# GS_01_Pow.net
KiCad netlist of a schematic drawn in Altium Designer
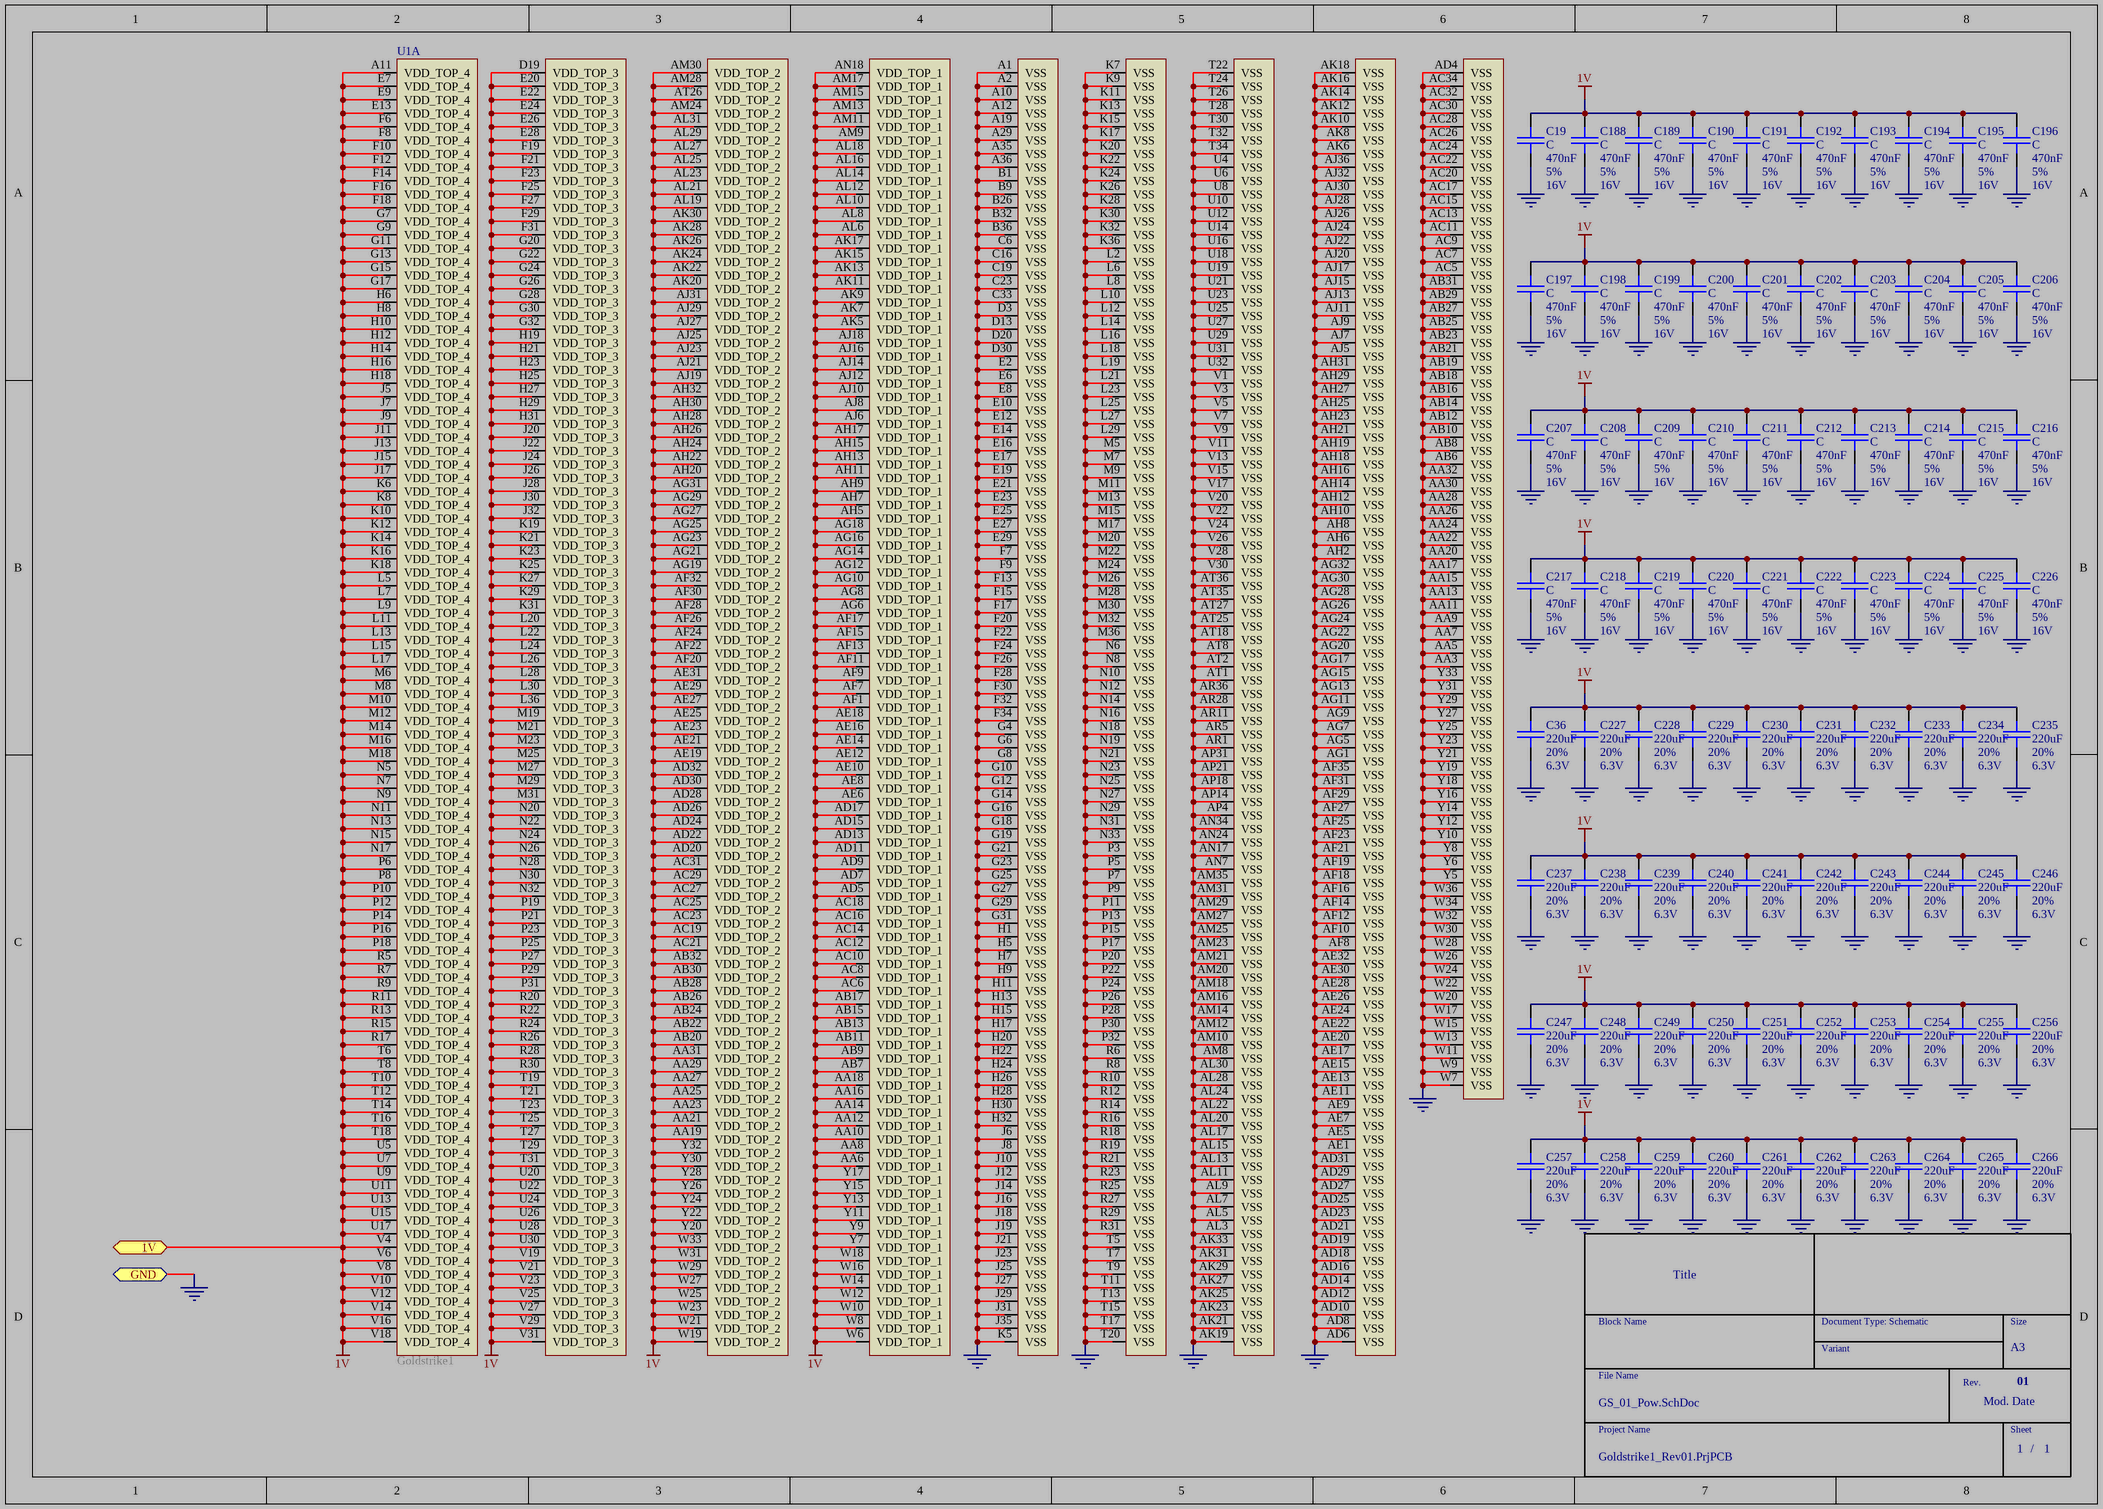
[diagram p0: GS_01_Pow.SchDoc]

(export (version "E")
  (design (tool "Eeschema 10.0.6"))
  (components
    (comp (ref "C19")
      (value "C")
      (footprint "SMD_0603_CAPC1608X95N")
      (fields
        (field (name "DB_PART_NUMBER") "CAP000028169")
        (field (name "DB_VALUE") "470nF")
        (field (name "DB_TOLERANCE") "5%")
        (field (name "DB_VOLTAGE") "16V")
        (field (name "DB_MANUFACTURER_PART") "KEMET    C0603C474J4RAC")
      )
      (libsource (lib "Database_Libs1") (part "C"))
    )
    (comp (ref "C36")
      (value "C")
      (footprint "SMD_1210_CAPC3225X279N")
      (fields
        (field (name "DB_PART_NUMBER") "CAP000047355")
        (field (name "DB_VALUE") "220uF")
        (field (name "DB_TOLERANCE") "20%")
        (field (name "DB_VOLTAGE") "6.3V")
        (field (name "DB_MANUFACTURER_PART") "SAMSUNG    CL32A227MQVNNNE")
        (field (name "DB_APPROVED_BY") "VSN")
      )
      (libsource (lib "Database_Libs1") (part "C"))
    )
    (comp (ref "C188")
      (value "C")
      (footprint "SMD_0603_CAPC1608X95N")
      (fields
        (field (name "DB_PART_NUMBER") "CAP000028169")
        (field (name "DB_VALUE") "470nF")
        (field (name "DB_TOLERANCE") "5%")
        (field (name "DB_VOLTAGE") "16V")
        (field (name "DB_MANUFACTURER_PART") "KEMET    C0603C474J4RAC")
      )
      (libsource (lib "Database_Libs1") (part "C"))
    )
    (comp (ref "C189")
      (value "C")
      (footprint "SMD_0603_CAPC1608X95N")
      (fields
        (field (name "DB_PART_NUMBER") "CAP000028169")
        (field (name "DB_VALUE") "470nF")
        (field (name "DB_TOLERANCE") "5%")
        (field (name "DB_VOLTAGE") "16V")
        (field (name "DB_MANUFACTURER_PART") "KEMET    C0603C474J4RAC")
      )
      (libsource (lib "Database_Libs1") (part "C"))
    )
    (comp (ref "C190")
      (value "C")
      (footprint "SMD_0603_CAPC1608X95N")
      (fields
        (field (name "DB_PART_NUMBER") "CAP000028169")
        (field (name "DB_VALUE") "470nF")
        (field (name "DB_TOLERANCE") "5%")
        (field (name "DB_VOLTAGE") "16V")
        (field (name "DB_MANUFACTURER_PART") "KEMET    C0603C474J4RAC")
      )
      (libsource (lib "Database_Libs1") (part "C"))
    )
    (comp (ref "C191")
      (value "C")
      (footprint "SMD_0603_CAPC1608X95N")
      (fields
        (field (name "DB_PART_NUMBER") "CAP000028169")
        (field (name "DB_VALUE") "470nF")
        (field (name "DB_TOLERANCE") "5%")
        (field (name "DB_VOLTAGE") "16V")
        (field (name "DB_MANUFACTURER_PART") "KEMET    C0603C474J4RAC")
      )
      (libsource (lib "Database_Libs1") (part "C"))
    )
    (comp (ref "C192")
      (value "C")
      (footprint "SMD_0603_CAPC1608X95N")
      (fields
        (field (name "DB_PART_NUMBER") "CAP000028169")
        (field (name "DB_VALUE") "470nF")
        (field (name "DB_TOLERANCE") "5%")
        (field (name "DB_VOLTAGE") "16V")
        (field (name "DB_MANUFACTURER_PART") "KEMET    C0603C474J4RAC")
      )
      (libsource (lib "Database_Libs1") (part "C"))
    )
    (comp (ref "C193")
      (value "C")
      (footprint "SMD_0603_CAPC1608X95N")
      (fields
        (field (name "DB_PART_NUMBER") "CAP000028169")
        (field (name "DB_VALUE") "470nF")
        (field (name "DB_TOLERANCE") "5%")
        (field (name "DB_VOLTAGE") "16V")
        (field (name "DB_MANUFACTURER_PART") "KEMET    C0603C474J4RAC")
      )
      (libsource (lib "Database_Libs1") (part "C"))
    )
    (comp (ref "C194")
      (value "C")
      (footprint "SMD_0603_CAPC1608X95N")
      (fields
        (field (name "DB_PART_NUMBER") "CAP000028169")
        (field (name "DB_VALUE") "470nF")
        (field (name "DB_TOLERANCE") "5%")
        (field (name "DB_VOLTAGE") "16V")
        (field (name "DB_MANUFACTURER_PART") "KEMET    C0603C474J4RAC")
      )
      (libsource (lib "Database_Libs1") (part "C"))
    )
    (comp (ref "C195")
      (value "C")
      (footprint "SMD_0603_CAPC1608X95N")
      (fields
        (field (name "DB_PART_NUMBER") "CAP000028169")
        (field (name "DB_VALUE") "470nF")
        (field (name "DB_TOLERANCE") "5%")
        (field (name "DB_VOLTAGE") "16V")
        (field (name "DB_MANUFACTURER_PART") "KEMET    C0603C474J4RAC")
      )
      (libsource (lib "Database_Libs1") (part "C"))
    )
    (comp (ref "C196")
      (value "C")
      (footprint "SMD_0603_CAPC1608X95N")
      (fields
        (field (name "DB_PART_NUMBER") "CAP000028169")
        (field (name "DB_VALUE") "470nF")
        (field (name "DB_TOLERANCE") "5%")
        (field (name "DB_VOLTAGE") "16V")
        (field (name "DB_MANUFACTURER_PART") "KEMET    C0603C474J4RAC")
      )
      (libsource (lib "Database_Libs1") (part "C"))
    )
    (comp (ref "C197")
      (value "C")
      (footprint "SMD_0603_CAPC1608X95N")
      (fields
        (field (name "DB_PART_NUMBER") "CAP000028169")
        (field (name "DB_VALUE") "470nF")
        (field (name "DB_TOLERANCE") "5%")
        (field (name "DB_VOLTAGE") "16V")
        (field (name "DB_MANUFACTURER_PART") "KEMET    C0603C474J4RAC")
      )
      (libsource (lib "Database_Libs1") (part "C"))
    )
    (comp (ref "C198")
      (value "C")
      (footprint "SMD_0603_CAPC1608X95N")
      (fields
        (field (name "DB_PART_NUMBER") "CAP000028169")
        (field (name "DB_VALUE") "470nF")
        (field (name "DB_TOLERANCE") "5%")
        (field (name "DB_VOLTAGE") "16V")
        (field (name "DB_MANUFACTURER_PART") "KEMET    C0603C474J4RAC")
      )
      (libsource (lib "Database_Libs1") (part "C"))
    )
    (comp (ref "C199")
      (value "C")
      (footprint "SMD_0603_CAPC1608X95N")
      (fields
        (field (name "DB_PART_NUMBER") "CAP000028169")
        (field (name "DB_VALUE") "470nF")
        (field (name "DB_TOLERANCE") "5%")
        (field (name "DB_VOLTAGE") "16V")
        (field (name "DB_MANUFACTURER_PART") "KEMET    C0603C474J4RAC")
      )
      (libsource (lib "Database_Libs1") (part "C"))
    )
    (comp (ref "C200")
      (value "C")
      (footprint "SMD_0603_CAPC1608X95N")
      (fields
        (field (name "DB_PART_NUMBER") "CAP000028169")
        (field (name "DB_VALUE") "470nF")
        (field (name "DB_TOLERANCE") "5%")
        (field (name "DB_VOLTAGE") "16V")
        (field (name "DB_MANUFACTURER_PART") "KEMET    C0603C474J4RAC")
      )
      (libsource (lib "Database_Libs1") (part "C"))
    )
    (comp (ref "C201")
      (value "C")
      (footprint "SMD_0603_CAPC1608X95N")
      (fields
        (field (name "DB_PART_NUMBER") "CAP000028169")
        (field (name "DB_VALUE") "470nF")
        (field (name "DB_TOLERANCE") "5%")
        (field (name "DB_VOLTAGE") "16V")
        (field (name "DB_MANUFACTURER_PART") "KEMET    C0603C474J4RAC")
      )
      (libsource (lib "Database_Libs1") (part "C"))
    )
    (comp (ref "C202")
      (value "C")
      (footprint "SMD_0603_CAPC1608X95N")
      (fields
        (field (name "DB_PART_NUMBER") "CAP000028169")
        (field (name "DB_VALUE") "470nF")
        (field (name "DB_TOLERANCE") "5%")
        (field (name "DB_VOLTAGE") "16V")
        (field (name "DB_MANUFACTURER_PART") "KEMET    C0603C474J4RAC")
      )
      (libsource (lib "Database_Libs1") (part "C"))
    )
    (comp (ref "C203")
      (value "C")
      (footprint "SMD_0603_CAPC1608X95N")
      (fields
        (field (name "DB_PART_NUMBER") "CAP000028169")
        (field (name "DB_VALUE") "470nF")
        (field (name "DB_TOLERANCE") "5%")
        (field (name "DB_VOLTAGE") "16V")
        (field (name "DB_MANUFACTURER_PART") "KEMET    C0603C474J4RAC")
      )
      (libsource (lib "Database_Libs1") (part "C"))
    )
    (comp (ref "C204")
      (value "C")
      (footprint "SMD_0603_CAPC1608X95N")
      (fields
        (field (name "DB_PART_NUMBER") "CAP000028169")
        (field (name "DB_VALUE") "470nF")
        (field (name "DB_TOLERANCE") "5%")
        (field (name "DB_VOLTAGE") "16V")
        (field (name "DB_MANUFACTURER_PART") "KEMET    C0603C474J4RAC")
      )
      (libsource (lib "Database_Libs1") (part "C"))
    )
    (comp (ref "C205")
      (value "C")
      (footprint "SMD_0603_CAPC1608X95N")
      (fields
        (field (name "DB_PART_NUMBER") "CAP000028169")
        (field (name "DB_VALUE") "470nF")
        (field (name "DB_TOLERANCE") "5%")
        (field (name "DB_VOLTAGE") "16V")
        (field (name "DB_MANUFACTURER_PART") "KEMET    C0603C474J4RAC")
      )
      (libsource (lib "Database_Libs1") (part "C"))
    )
    (comp (ref "C206")
      (value "C")
      (footprint "SMD_0603_CAPC1608X95N")
      (fields
        (field (name "DB_PART_NUMBER") "CAP000028169")
        (field (name "DB_VALUE") "470nF")
        (field (name "DB_TOLERANCE") "5%")
        (field (name "DB_VOLTAGE") "16V")
        (field (name "DB_MANUFACTURER_PART") "KEMET    C0603C474J4RAC")
      )
      (libsource (lib "Database_Libs1") (part "C"))
    )
    (comp (ref "C207")
      (value "C")
      (footprint "SMD_0603_CAPC1608X95N")
      (fields
        (field (name "DB_PART_NUMBER") "CAP000028169")
        (field (name "DB_VALUE") "470nF")
        (field (name "DB_TOLERANCE") "5%")
        (field (name "DB_VOLTAGE") "16V")
        (field (name "DB_MANUFACTURER_PART") "KEMET    C0603C474J4RAC")
      )
      (libsource (lib "Database_Libs1") (part "C"))
    )
    (comp (ref "C208")
      (value "C")
      (footprint "SMD_0603_CAPC1608X95N")
      (fields
        (field (name "DB_PART_NUMBER") "CAP000028169")
        (field (name "DB_VALUE") "470nF")
        (field (name "DB_TOLERANCE") "5%")
        (field (name "DB_VOLTAGE") "16V")
        (field (name "DB_MANUFACTURER_PART") "KEMET    C0603C474J4RAC")
      )
      (libsource (lib "Database_Libs1") (part "C"))
    )
    (comp (ref "C209")
      (value "C")
      (footprint "SMD_0603_CAPC1608X95N")
      (fields
        (field (name "DB_PART_NUMBER") "CAP000028169")
        (field (name "DB_VALUE") "470nF")
        (field (name "DB_TOLERANCE") "5%")
        (field (name "DB_VOLTAGE") "16V")
        (field (name "DB_MANUFACTURER_PART") "KEMET    C0603C474J4RAC")
      )
      (libsource (lib "Database_Libs1") (part "C"))
    )
    (comp (ref "C210")
      (value "C")
      (footprint "SMD_0603_CAPC1608X95N")
      (fields
        (field (name "DB_PART_NUMBER") "CAP000028169")
        (field (name "DB_VALUE") "470nF")
        (field (name "DB_TOLERANCE") "5%")
        (field (name "DB_VOLTAGE") "16V")
        (field (name "DB_MANUFACTURER_PART") "KEMET    C0603C474J4RAC")
      )
      (libsource (lib "Database_Libs1") (part "C"))
    )
    (comp (ref "C211")
      (value "C")
      (footprint "SMD_0603_CAPC1608X95N")
      (fields
        (field (name "DB_PART_NUMBER") "CAP000028169")
        (field (name "DB_VALUE") "470nF")
        (field (name "DB_TOLERANCE") "5%")
        (field (name "DB_VOLTAGE") "16V")
        (field (name "DB_MANUFACTURER_PART") "KEMET    C0603C474J4RAC")
      )
      (libsource (lib "Database_Libs1") (part "C"))
    )
    (comp (ref "C212")
      (value "C")
      (footprint "SMD_0603_CAPC1608X95N")
      (fields
        (field (name "DB_PART_NUMBER") "CAP000028169")
        (field (name "DB_VALUE") "470nF")
        (field (name "DB_TOLERANCE") "5%")
        (field (name "DB_VOLTAGE") "16V")
        (field (name "DB_MANUFACTURER_PART") "KEMET    C0603C474J4RAC")
      )
      (libsource (lib "Database_Libs1") (part "C"))
    )
    (comp (ref "C213")
      (value "C")
      (footprint "SMD_0603_CAPC1608X95N")
      (fields
        (field (name "DB_PART_NUMBER") "CAP000028169")
        (field (name "DB_VALUE") "470nF")
        (field (name "DB_TOLERANCE") "5%")
        (field (name "DB_VOLTAGE") "16V")
        (field (name "DB_MANUFACTURER_PART") "KEMET    C0603C474J4RAC")
      )
      (libsource (lib "Database_Libs1") (part "C"))
    )
    (comp (ref "C214")
      (value "C")
      (footprint "SMD_0603_CAPC1608X95N")
      (fields
        (field (name "DB_PART_NUMBER") "CAP000028169")
        (field (name "DB_VALUE") "470nF")
        (field (name "DB_TOLERANCE") "5%")
        (field (name "DB_VOLTAGE") "16V")
        (field (name "DB_MANUFACTURER_PART") "KEMET    C0603C474J4RAC")
      )
      (libsource (lib "Database_Libs1") (part "C"))
    )
    (comp (ref "C215")
      (value "C")
      (footprint "SMD_0603_CAPC1608X95N")
      (fields
        (field (name "DB_PART_NUMBER") "CAP000028169")
        (field (name "DB_VALUE") "470nF")
        (field (name "DB_TOLERANCE") "5%")
        (field (name "DB_VOLTAGE") "16V")
        (field (name "DB_MANUFACTURER_PART") "KEMET    C0603C474J4RAC")
      )
      (libsource (lib "Database_Libs1") (part "C"))
    )
    (comp (ref "C216")
      (value "C")
      (footprint "SMD_0603_CAPC1608X95N")
      (fields
        (field (name "DB_PART_NUMBER") "CAP000028169")
        (field (name "DB_VALUE") "470nF")
        (field (name "DB_TOLERANCE") "5%")
        (field (name "DB_VOLTAGE") "16V")
        (field (name "DB_MANUFACTURER_PART") "KEMET    C0603C474J4RAC")
      )
      (libsource (lib "Database_Libs1") (part "C"))
    )
    (comp (ref "C217")
      (value "C")
      (footprint "SMD_0603_CAPC1608X95N")
      (fields
        (field (name "DB_PART_NUMBER") "CAP000028169")
        (field (name "DB_VALUE") "470nF")
        (field (name "DB_TOLERANCE") "5%")
        (field (name "DB_VOLTAGE") "16V")
        (field (name "DB_MANUFACTURER_PART") "KEMET    C0603C474J4RAC")
      )
      (libsource (lib "Database_Libs1") (part "C"))
    )
    (comp (ref "C218")
      (value "C")
      (footprint "SMD_0603_CAPC1608X95N")
      (fields
        (field (name "DB_PART_NUMBER") "CAP000028169")
        (field (name "DB_VALUE") "470nF")
        (field (name "DB_TOLERANCE") "5%")
        (field (name "DB_VOLTAGE") "16V")
        (field (name "DB_MANUFACTURER_PART") "KEMET    C0603C474J4RAC")
      )
      (libsource (lib "Database_Libs1") (part "C"))
    )
    (comp (ref "C219")
      (value "C")
      (footprint "SMD_0603_CAPC1608X95N")
      (fields
        (field (name "DB_PART_NUMBER") "CAP000028169")
        (field (name "DB_VALUE") "470nF")
        (field (name "DB_TOLERANCE") "5%")
        (field (name "DB_VOLTAGE") "16V")
        (field (name "DB_MANUFACTURER_PART") "KEMET    C0603C474J4RAC")
      )
      (libsource (lib "Database_Libs1") (part "C"))
    )
    (comp (ref "C220")
      (value "C")
      (footprint "SMD_0603_CAPC1608X95N")
      (fields
        (field (name "DB_PART_NUMBER") "CAP000028169")
        (field (name "DB_VALUE") "470nF")
        (field (name "DB_TOLERANCE") "5%")
        (field (name "DB_VOLTAGE") "16V")
        (field (name "DB_MANUFACTURER_PART") "KEMET    C0603C474J4RAC")
      )
      (libsource (lib "Database_Libs1") (part "C"))
    )
    (comp (ref "C221")
      (value "C")
      (footprint "SMD_0603_CAPC1608X95N")
      (fields
        (field (name "DB_PART_NUMBER") "CAP000028169")
        (field (name "DB_VALUE") "470nF")
        (field (name "DB_TOLERANCE") "5%")
        (field (name "DB_VOLTAGE") "16V")
        (field (name "DB_MANUFACTURER_PART") "KEMET    C0603C474J4RAC")
      )
      (libsource (lib "Database_Libs1") (part "C"))
    )
    (comp (ref "C222")
      (value "C")
      (footprint "SMD_0603_CAPC1608X95N")
      (fields
        (field (name "DB_PART_NUMBER") "CAP000028169")
        (field (name "DB_VALUE") "470nF")
        (field (name "DB_TOLERANCE") "5%")
        (field (name "DB_VOLTAGE") "16V")
        (field (name "DB_MANUFACTURER_PART") "KEMET    C0603C474J4RAC")
      )
      (libsource (lib "Database_Libs1") (part "C"))
    )
    (comp (ref "C223")
      (value "C")
      (footprint "SMD_0603_CAPC1608X95N")
      (fields
        (field (name "DB_PART_NUMBER") "CAP000028169")
        (field (name "DB_VALUE") "470nF")
        (field (name "DB_TOLERANCE") "5%")
        (field (name "DB_VOLTAGE") "16V")
        (field (name "DB_MANUFACTURER_PART") "KEMET    C0603C474J4RAC")
      )
      (libsource (lib "Database_Libs1") (part "C"))
    )
    (comp (ref "C224")
      (value "C")
      (footprint "SMD_0603_CAPC1608X95N")
      (fields
        (field (name "DB_PART_NUMBER") "CAP000028169")
        (field (name "DB_VALUE") "470nF")
        (field (name "DB_TOLERANCE") "5%")
        (field (name "DB_VOLTAGE") "16V")
        (field (name "DB_MANUFACTURER_PART") "KEMET    C0603C474J4RAC")
      )
      (libsource (lib "Database_Libs1") (part "C"))
    )
    (comp (ref "C225")
      (value "C")
      (footprint "SMD_0603_CAPC1608X95N")
      (fields
        (field (name "DB_PART_NUMBER") "CAP000028169")
        (field (name "DB_VALUE") "470nF")
        (field (name "DB_TOLERANCE") "5%")
        (field (name "DB_VOLTAGE") "16V")
        (field (name "DB_MANUFACTURER_PART") "KEMET    C0603C474J4RAC")
      )
      (libsource (lib "Database_Libs1") (part "C"))
    )
    (comp (ref "C226")
      (value "C")
      (footprint "SMD_0603_CAPC1608X95N")
      (fields
        (field (name "DB_PART_NUMBER") "CAP000028169")
        (field (name "DB_VALUE") "470nF")
        (field (name "DB_TOLERANCE") "5%")
        (field (name "DB_VOLTAGE") "16V")
        (field (name "DB_MANUFACTURER_PART") "KEMET    C0603C474J4RAC")
      )
      (libsource (lib "Database_Libs1") (part "C"))
    )
    (comp (ref "C227")
      (value "C")
      (footprint "SMD_1210_CAPC3225X279N")
      (fields
        (field (name "DB_PART_NUMBER") "CAP000047355")
        (field (name "DB_VALUE") "220uF")
        (field (name "DB_TOLERANCE") "20%")
        (field (name "DB_VOLTAGE") "6.3V")
        (field (name "DB_MANUFACTURER_PART") "SAMSUNG    CL32A227MQVNNNE")
        (field (name "DB_APPROVED_BY") "VSN")
      )
      (libsource (lib "Database_Libs1") (part "C"))
    )
    (comp (ref "C228")
      (value "C")
      (footprint "SMD_1210_CAPC3225X279N")
      (fields
        (field (name "DB_PART_NUMBER") "CAP000047355")
        (field (name "DB_VALUE") "220uF")
        (field (name "DB_TOLERANCE") "20%")
        (field (name "DB_VOLTAGE") "6.3V")
        (field (name "DB_MANUFACTURER_PART") "SAMSUNG    CL32A227MQVNNNE")
        (field (name "DB_APPROVED_BY") "VSN")
      )
      (libsource (lib "Database_Libs1") (part "C"))
    )
    (comp (ref "C229")
      (value "C")
      (footprint "SMD_1210_CAPC3225X279N")
      (fields
        (field (name "DB_PART_NUMBER") "CAP000047355")
        (field (name "DB_VALUE") "220uF")
        (field (name "DB_TOLERANCE") "20%")
        (field (name "DB_VOLTAGE") "6.3V")
        (field (name "DB_MANUFACTURER_PART") "SAMSUNG    CL32A227MQVNNNE")
        (field (name "DB_APPROVED_BY") "VSN")
      )
      (libsource (lib "Database_Libs1") (part "C"))
    )
    (comp (ref "C230")
      (value "C")
      (footprint "SMD_1210_CAPC3225X279N")
      (fields
        (field (name "DB_PART_NUMBER") "CAP000047355")
        (field (name "DB_VALUE") "220uF")
        (field (name "DB_TOLERANCE") "20%")
        (field (name "DB_VOLTAGE") "6.3V")
        (field (name "DB_MANUFACTURER_PART") "SAMSUNG    CL32A227MQVNNNE")
        (field (name "DB_APPROVED_BY") "VSN")
      )
      (libsource (lib "Database_Libs1") (part "C"))
    )
    (comp (ref "C231")
      (value "C")
      (footprint "SMD_1210_CAPC3225X279N")
      (fields
        (field (name "DB_PART_NUMBER") "CAP000047355")
        (field (name "DB_VALUE") "220uF")
        (field (name "DB_TOLERANCE") "20%")
        (field (name "DB_VOLTAGE") "6.3V")
        (field (name "DB_MANUFACTURER_PART") "SAMSUNG    CL32A227MQVNNNE")
        (field (name "DB_APPROVED_BY") "VSN")
      )
      (libsource (lib "Database_Libs1") (part "C"))
    )
    (comp (ref "C232")
      (value "C")
      (footprint "SMD_1210_CAPC3225X279N")
      (fields
        (field (name "DB_PART_NUMBER") "CAP000047355")
        (field (name "DB_VALUE") "220uF")
        (field (name "DB_TOLERANCE") "20%")
        (field (name "DB_VOLTAGE") "6.3V")
        (field (name "DB_MANUFACTURER_PART") "SAMSUNG    CL32A227MQVNNNE")
        (field (name "DB_APPROVED_BY") "VSN")
      )
      (libsource (lib "Database_Libs1") (part "C"))
    )
    (comp (ref "C233")
      (value "C")
      (footprint "SMD_1210_CAPC3225X279N")
      (fields
        (field (name "DB_PART_NUMBER") "CAP000047355")
        (field (name "DB_VALUE") "220uF")
        (field (name "DB_TOLERANCE") "20%")
        (field (name "DB_VOLTAGE") "6.3V")
        (field (name "DB_MANUFACTURER_PART") "SAMSUNG    CL32A227MQVNNNE")
        (field (name "DB_APPROVED_BY") "VSN")
      )
      (libsource (lib "Database_Libs1") (part "C"))
    )
    (comp (ref "C234")
      (value "C")
      (footprint "SMD_1210_CAPC3225X279N")
      (fields
        (field (name "DB_PART_NUMBER") "CAP000047355")
        (field (name "DB_VALUE") "220uF")
        (field (name "DB_TOLERANCE") "20%")
        (field (name "DB_VOLTAGE") "6.3V")
        (field (name "DB_MANUFACTURER_PART") "SAMSUNG    CL32A227MQVNNNE")
        (field (name "DB_APPROVED_BY") "VSN")
      )
      (libsource (lib "Database_Libs1") (part "C"))
    )
    (comp (ref "C235")
      (value "C")
      (footprint "SMD_1210_CAPC3225X279N")
      (fields
        (field (name "DB_PART_NUMBER") "CAP000047355")
        (field (name "DB_VALUE") "220uF")
        (field (name "DB_TOLERANCE") "20%")
        (field (name "DB_VOLTAGE") "6.3V")
        (field (name "DB_MANUFACTURER_PART") "SAMSUNG    CL32A227MQVNNNE")
        (field (name "DB_APPROVED_BY") "VSN")
      )
      (libsource (lib "Database_Libs1") (part "C"))
    )
    (comp (ref "C237")
      (value "C")
      (footprint "SMD_1210_CAPC3225X279N")
      (fields
        (field (name "DB_PART_NUMBER") "CAP000047355")
        (field (name "DB_VALUE") "220uF")
        (field (name "DB_TOLERANCE") "20%")
        (field (name "DB_VOLTAGE") "6.3V")
        (field (name "DB_MANUFACTURER_PART") "SAMSUNG    CL32A227MQVNNNE")
        (field (name "DB_APPROVED_BY") "VSN")
      )
      (libsource (lib "Database_Libs1") (part "C"))
    )
    (comp (ref "C238")
      (value "C")
      (footprint "SMD_1210_CAPC3225X279N")
      (fields
        (field (name "DB_PART_NUMBER") "CAP000047355")
        (field (name "DB_VALUE") "220uF")
        (field (name "DB_TOLERANCE") "20%")
        (field (name "DB_VOLTAGE") "6.3V")
        (field (name "DB_MANUFACTURER_PART") "SAMSUNG    CL32A227MQVNNNE")
        (field (name "DB_APPROVED_BY") "VSN")
      )
      (libsource (lib "Database_Libs1") (part "C"))
    )
    (comp (ref "C239")
      (value "C")
      (footprint "SMD_1210_CAPC3225X279N")
      (fields
        (field (name "DB_PART_NUMBER") "CAP000047355")
        (field (name "DB_VALUE") "220uF")
        (field (name "DB_TOLERANCE") "20%")
        (field (name "DB_VOLTAGE") "6.3V")
        (field (name "DB_MANUFACTURER_PART") "SAMSUNG    CL32A227MQVNNNE")
        (field (name "DB_APPROVED_BY") "VSN")
      )
      (libsource (lib "Database_Libs1") (part "C"))
    )
    (comp (ref "C240")
      (value "C")
      (footprint "SMD_1210_CAPC3225X279N")
      (fields
        (field (name "DB_PART_NUMBER") "CAP000047355")
        (field (name "DB_VALUE") "220uF")
        (field (name "DB_TOLERANCE") "20%")
        (field (name "DB_VOLTAGE") "6.3V")
        (field (name "DB_MANUFACTURER_PART") "SAMSUNG    CL32A227MQVNNNE")
        (field (name "DB_APPROVED_BY") "VSN")
      )
      (libsource (lib "Database_Libs1") (part "C"))
    )
    (comp (ref "C241")
      (value "C")
      (footprint "SMD_1210_CAPC3225X279N")
      (fields
        (field (name "DB_PART_NUMBER") "CAP000047355")
        (field (name "DB_VALUE") "220uF")
        (field (name "DB_TOLERANCE") "20%")
        (field (name "DB_VOLTAGE") "6.3V")
        (field (name "DB_MANUFACTURER_PART") "SAMSUNG    CL32A227MQVNNNE")
        (field (name "DB_APPROVED_BY") "VSN")
      )
      (libsource (lib "Database_Libs1") (part "C"))
    )
    (comp (ref "C242")
      (value "C")
      (footprint "SMD_1210_CAPC3225X279N")
      (fields
        (field (name "DB_PART_NUMBER") "CAP000047355")
        (field (name "DB_VALUE") "220uF")
        (field (name "DB_TOLERANCE") "20%")
        (field (name "DB_VOLTAGE") "6.3V")
        (field (name "DB_MANUFACTURER_PART") "SAMSUNG    CL32A227MQVNNNE")
        (field (name "DB_APPROVED_BY") "VSN")
      )
      (libsource (lib "Database_Libs1") (part "C"))
    )
    (comp (ref "C243")
      (value "C")
      (footprint "SMD_1210_CAPC3225X279N")
      (fields
        (field (name "DB_PART_NUMBER") "CAP000047355")
        (field (name "DB_VALUE") "220uF")
        (field (name "DB_TOLERANCE") "20%")
        (field (name "DB_VOLTAGE") "6.3V")
        (field (name "DB_MANUFACTURER_PART") "SAMSUNG    CL32A227MQVNNNE")
        (field (name "DB_APPROVED_BY") "VSN")
      )
      (libsource (lib "Database_Libs1") (part "C"))
    )
    (comp (ref "C244")
      (value "C")
      (footprint "SMD_1210_CAPC3225X279N")
      (fields
        (field (name "DB_PART_NUMBER") "CAP000047355")
        (field (name "DB_VALUE") "220uF")
        (field (name "DB_TOLERANCE") "20%")
        (field (name "DB_VOLTAGE") "6.3V")
        (field (name "DB_MANUFACTURER_PART") "SAMSUNG    CL32A227MQVNNNE")
        (field (name "DB_APPROVED_BY") "VSN")
      )
      (libsource (lib "Database_Libs1") (part "C"))
    )
    (comp (ref "C245")
      (value "C")
      (footprint "SMD_1210_CAPC3225X279N")
      (fields
        (field (name "DB_PART_NUMBER") "CAP000047355")
        (field (name "DB_VALUE") "220uF")
        (field (name "DB_TOLERANCE") "20%")
        (field (name "DB_VOLTAGE") "6.3V")
        (field (name "DB_MANUFACTURER_PART") "SAMSUNG    CL32A227MQVNNNE")
        (field (name "DB_APPROVED_BY") "VSN")
      )
      (libsource (lib "Database_Libs1") (part "C"))
    )
    (comp (ref "C246")
      (value "C")
      (footprint "SMD_1210_CAPC3225X279N")
      (fields
        (field (name "DB_PART_NUMBER") "CAP000047355")
        (field (name "DB_VALUE") "220uF")
        (field (name "DB_TOLERANCE") "20%")
        (field (name "DB_VOLTAGE") "6.3V")
        (field (name "DB_MANUFACTURER_PART") "SAMSUNG    CL32A227MQVNNNE")
        (field (name "DB_APPROVED_BY") "VSN")
      )
      (libsource (lib "Database_Libs1") (part "C"))
    )
    (comp (ref "C247")
      (value "C")
      (footprint "SMD_1210_CAPC3225X279N")
      (fields
        (field (name "DB_PART_NUMBER") "CAP000047355")
        (field (name "DB_VALUE") "220uF")
        (field (name "DB_TOLERANCE") "20%")
        (field (name "DB_VOLTAGE") "6.3V")
        (field (name "DB_MANUFACTURER_PART") "SAMSUNG    CL32A227MQVNNNE")
        (field (name "DB_APPROVED_BY") "VSN")
      )
      (libsource (lib "Database_Libs1") (part "C"))
    )
    (comp (ref "C248")
      (value "C")
      (footprint "SMD_1210_CAPC3225X279N")
      (fields
        (field (name "DB_PART_NUMBER") "CAP000047355")
        (field (name "DB_VALUE") "220uF")
        (field (name "DB_TOLERANCE") "20%")
        (field (name "DB_VOLTAGE") "6.3V")
        (field (name "DB_MANUFACTURER_PART") "SAMSUNG    CL32A227MQVNNNE")
        (field (name "DB_APPROVED_BY") "VSN")
      )
      (libsource (lib "Database_Libs1") (part "C"))
    )
    (comp (ref "C249")
      (value "C")
      (footprint "SMD_1210_CAPC3225X279N")
      (fields
        (field (name "DB_PART_NUMBER") "CAP000047355")
        (field (name "DB_VALUE") "220uF")
        (field (name "DB_TOLERANCE") "20%")
        (field (name "DB_VOLTAGE") "6.3V")
        (field (name "DB_MANUFACTURER_PART") "SAMSUNG    CL32A227MQVNNNE")
        (field (name "DB_APPROVED_BY") "VSN")
      )
      (libsource (lib "Database_Libs1") (part "C"))
    )
    (comp (ref "C250")
      (value "C")
      (footprint "SMD_1210_CAPC3225X279N")
      (fields
        (field (name "DB_PART_NUMBER") "CAP000047355")
        (field (name "DB_VALUE") "220uF")
        (field (name "DB_TOLERANCE") "20%")
        (field (name "DB_VOLTAGE") "6.3V")
        (field (name "DB_MANUFACTURER_PART") "SAMSUNG    CL32A227MQVNNNE")
        (field (name "DB_APPROVED_BY") "VSN")
      )
      (libsource (lib "Database_Libs1") (part "C"))
    )
    (comp (ref "C251")
      (value "C")
      (footprint "SMD_1210_CAPC3225X279N")
      (fields
        (field (name "DB_PART_NUMBER") "CAP000047355")
        (field (name "DB_VALUE") "220uF")
        (field (name "DB_TOLERANCE") "20%")
        (field (name "DB_VOLTAGE") "6.3V")
        (field (name "DB_MANUFACTURER_PART") "SAMSUNG    CL32A227MQVNNNE")
        (field (name "DB_APPROVED_BY") "VSN")
      )
      (libsource (lib "Database_Libs1") (part "C"))
    )
    (comp (ref "C252")
      (value "C")
      (footprint "SMD_1210_CAPC3225X279N")
      (fields
        (field (name "DB_PART_NUMBER") "CAP000047355")
        (field (name "DB_VALUE") "220uF")
        (field (name "DB_TOLERANCE") "20%")
        (field (name "DB_VOLTAGE") "6.3V")
        (field (name "DB_MANUFACTURER_PART") "SAMSUNG    CL32A227MQVNNNE")
        (field (name "DB_APPROVED_BY") "VSN")
      )
      (libsource (lib "Database_Libs1") (part "C"))
    )
    (comp (ref "C253")
      (value "C")
      (footprint "SMD_1210_CAPC3225X279N")
      (fields
        (field (name "DB_PART_NUMBER") "CAP000047355")
        (field (name "DB_VALUE") "220uF")
        (field (name "DB_TOLERANCE") "20%")
        (field (name "DB_VOLTAGE") "6.3V")
        (field (name "DB_MANUFACTURER_PART") "SAMSUNG    CL32A227MQVNNNE")
        (field (name "DB_APPROVED_BY") "VSN")
      )
      (libsource (lib "Database_Libs1") (part "C"))
    )
    (comp (ref "C254")
      (value "C")
      (footprint "SMD_1210_CAPC3225X279N")
      (fields
        (field (name "DB_PART_NUMBER") "CAP000047355")
        (field (name "DB_VALUE") "220uF")
        (field (name "DB_TOLERANCE") "20%")
        (field (name "DB_VOLTAGE") "6.3V")
        (field (name "DB_MANUFACTURER_PART") "SAMSUNG    CL32A227MQVNNNE")
        (field (name "DB_APPROVED_BY") "VSN")
      )
      (libsource (lib "Database_Libs1") (part "C"))
    )
    (comp (ref "C255")
      (value "C")
      (footprint "SMD_1210_CAPC3225X279N")
      (fields
        (field (name "DB_PART_NUMBER") "CAP000047355")
        (field (name "DB_VALUE") "220uF")
        (field (name "DB_TOLERANCE") "20%")
        (field (name "DB_VOLTAGE") "6.3V")
        (field (name "DB_MANUFACTURER_PART") "SAMSUNG    CL32A227MQVNNNE")
        (field (name "DB_APPROVED_BY") "VSN")
      )
      (libsource (lib "Database_Libs1") (part "C"))
    )
    (comp (ref "C256")
      (value "C")
      (footprint "SMD_1210_CAPC3225X279N")
      (fields
        (field (name "DB_PART_NUMBER") "CAP000047355")
        (field (name "DB_VALUE") "220uF")
        (field (name "DB_TOLERANCE") "20%")
        (field (name "DB_VOLTAGE") "6.3V")
        (field (name "DB_MANUFACTURER_PART") "SAMSUNG    CL32A227MQVNNNE")
        (field (name "DB_APPROVED_BY") "VSN")
      )
      (libsource (lib "Database_Libs1") (part "C"))
    )
    (comp (ref "C257")
      (value "C")
      (footprint "SMD_1210_CAPC3225X279N")
      (fields
        (field (name "DB_PART_NUMBER") "CAP000047355")
        (field (name "DB_VALUE") "220uF")
        (field (name "DB_TOLERANCE") "20%")
        (field (name "DB_VOLTAGE") "6.3V")
        (field (name "DB_MANUFACTURER_PART") "SAMSUNG    CL32A227MQVNNNE")
        (field (name "DB_APPROVED_BY") "VSN")
      )
      (libsource (lib "Database_Libs1") (part "C"))
    )
    (comp (ref "C258")
      (value "C")
      (footprint "SMD_1210_CAPC3225X279N")
      (fields
        (field (name "DB_PART_NUMBER") "CAP000047355")
        (field (name "DB_VALUE") "220uF")
        (field (name "DB_TOLERANCE") "20%")
        (field (name "DB_VOLTAGE") "6.3V")
        (field (name "DB_MANUFACTURER_PART") "SAMSUNG    CL32A227MQVNNNE")
        (field (name "DB_APPROVED_BY") "VSN")
      )
      (libsource (lib "Database_Libs1") (part "C"))
    )
    (comp (ref "C259")
      (value "C")
      (footprint "SMD_1210_CAPC3225X279N")
      (fields
        (field (name "DB_PART_NUMBER") "CAP000047355")
        (field (name "DB_VALUE") "220uF")
        (field (name "DB_TOLERANCE") "20%")
        (field (name "DB_VOLTAGE") "6.3V")
        (field (name "DB_MANUFACTURER_PART") "SAMSUNG    CL32A227MQVNNNE")
        (field (name "DB_APPROVED_BY") "VSN")
      )
      (libsource (lib "Database_Libs1") (part "C"))
    )
    (comp (ref "C260")
      (value "C")
      (footprint "SMD_1210_CAPC3225X279N")
      (fields
        (field (name "DB_PART_NUMBER") "CAP000047355")
        (field (name "DB_VALUE") "220uF")
        (field (name "DB_TOLERANCE") "20%")
        (field (name "DB_VOLTAGE") "6.3V")
        (field (name "DB_MANUFACTURER_PART") "SAMSUNG    CL32A227MQVNNNE")
        (field (name "DB_APPROVED_BY") "VSN")
      )
      (libsource (lib "Database_Libs1") (part "C"))
    )
    (comp (ref "C261")
      (value "C")
      (footprint "SMD_1210_CAPC3225X279N")
      (fields
        (field (name "DB_PART_NUMBER") "CAP000047355")
        (field (name "DB_VALUE") "220uF")
        (field (name "DB_TOLERANCE") "20%")
        (field (name "DB_VOLTAGE") "6.3V")
        (field (name "DB_MANUFACTURER_PART") "SAMSUNG    CL32A227MQVNNNE")
        (field (name "DB_APPROVED_BY") "VSN")
      )
      (libsource (lib "Database_Libs1") (part "C"))
    )
    (comp (ref "C262")
      (value "C")
      (footprint "SMD_1210_CAPC3225X279N")
      (fields
        (field (name "DB_PART_NUMBER") "CAP000047355")
        (field (name "DB_VALUE") "220uF")
        (field (name "DB_TOLERANCE") "20%")
        (field (name "DB_VOLTAGE") "6.3V")
        (field (name "DB_MANUFACTURER_PART") "SAMSUNG    CL32A227MQVNNNE")
        (field (name "DB_APPROVED_BY") "VSN")
      )
      (libsource (lib "Database_Libs1") (part "C"))
    )
    (comp (ref "C263")
      (value "C")
      (footprint "SMD_1210_CAPC3225X279N")
      (fields
        (field (name "DB_PART_NUMBER") "CAP000047355")
        (field (name "DB_VALUE") "220uF")
        (field (name "DB_TOLERANCE") "20%")
        (field (name "DB_VOLTAGE") "6.3V")
        (field (name "DB_MANUFACTURER_PART") "SAMSUNG    CL32A227MQVNNNE")
        (field (name "DB_APPROVED_BY") "VSN")
      )
      (libsource (lib "Database_Libs1") (part "C"))
    )
    (comp (ref "C264")
      (value "C")
      (footprint "SMD_1210_CAPC3225X279N")
      (fields
        (field (name "DB_PART_NUMBER") "CAP000047355")
        (field (name "DB_VALUE") "220uF")
        (field (name "DB_TOLERANCE") "20%")
        (field (name "DB_VOLTAGE") "6.3V")
        (field (name "DB_MANUFACTURER_PART") "SAMSUNG    CL32A227MQVNNNE")
        (field (name "DB_APPROVED_BY") "VSN")
      )
      (libsource (lib "Database_Libs1") (part "C"))
    )
    (comp (ref "C265")
      (value "C")
      (footprint "SMD_1210_CAPC3225X279N")
      (fields
        (field (name "DB_PART_NUMBER") "CAP000047355")
        (field (name "DB_VALUE") "220uF")
        (field (name "DB_TOLERANCE") "20%")
        (field (name "DB_VOLTAGE") "6.3V")
        (field (name "DB_MANUFACTURER_PART") "SAMSUNG    CL32A227MQVNNNE")
        (field (name "DB_APPROVED_BY") "VSN")
      )
      (libsource (lib "Database_Libs1") (part "C"))
    )
    (comp (ref "C266")
      (value "C")
      (footprint "SMD_1210_CAPC3225X279N")
      (fields
        (field (name "DB_PART_NUMBER") "CAP000047355")
        (field (name "DB_VALUE") "220uF")
        (field (name "DB_TOLERANCE") "20%")
        (field (name "DB_VOLTAGE") "6.3V")
        (field (name "DB_MANUFACTURER_PART") "SAMSUNG    CL32A227MQVNNNE")
        (field (name "DB_APPROVED_BY") "VSN")
      )
      (libsource (lib "Database_Libs1") (part "C"))
    )
    (comp (ref "U1")
      (value "Goldstrike1")
      (footprint "SMD_BGA1296C100P36X36")
      (libsource (lib "Schlib1") (part "Goldstrike1"))
    )
  )
  (nets
    (net (code "1") (name "1V") (class "Default")
      (node (ref "C188") (pin "2") (pinfunction "2_2") (pintype "passive"))
      (node (ref "C189") (pin "2") (pinfunction "2_2") (pintype "passive"))
      (node (ref "C19") (pin "2") (pinfunction "2_2") (pintype "passive"))
      (node (ref "C190") (pin "2") (pinfunction "2_2") (pintype "passive"))
      (node (ref "C191") (pin "2") (pinfunction "2_2") (pintype "passive"))
      (node (ref "C192") (pin "2") (pinfunction "2_2") (pintype "passive"))
      (node (ref "C193") (pin "2") (pinfunction "2_2") (pintype "passive"))
      (node (ref "C194") (pin "2") (pinfunction "2_2") (pintype "passive"))
      (node (ref "C195") (pin "2") (pinfunction "2_2") (pintype "passive"))
      (node (ref "C196") (pin "2") (pinfunction "2_2") (pintype "passive"))
      (node (ref "C197") (pin "2") (pinfunction "2_2") (pintype "passive"))
      (node (ref "C198") (pin "2") (pinfunction "2_2") (pintype "passive"))
      (node (ref "C199") (pin "2") (pinfunction "2_2") (pintype "passive"))
      (node (ref "C200") (pin "2") (pinfunction "2_2") (pintype "passive"))
      (node (ref "C201") (pin "2") (pinfunction "2_2") (pintype "passive"))
      (node (ref "C202") (pin "2") (pinfunction "2_2") (pintype "passive"))
      (node (ref "C203") (pin "2") (pinfunction "2_2") (pintype "passive"))
      (node (ref "C204") (pin "2") (pinfunction "2_2") (pintype "passive"))
      (node (ref "C205") (pin "2") (pinfunction "2_2") (pintype "passive"))
      (node (ref "C206") (pin "2") (pinfunction "2_2") (pintype "passive"))
      (node (ref "C207") (pin "2") (pinfunction "2_2") (pintype "passive"))
      (node (ref "C208") (pin "2") (pinfunction "2_2") (pintype "passive"))
      (node (ref "C209") (pin "2") (pinfunction "2_2") (pintype "passive"))
      (node (ref "C210") (pin "2") (pinfunction "2_2") (pintype "passive"))
      (node (ref "C211") (pin "2") (pinfunction "2_2") (pintype "passive"))
      (node (ref "C212") (pin "2") (pinfunction "2_2") (pintype "passive"))
      (node (ref "C213") (pin "2") (pinfunction "2_2") (pintype "passive"))
      (node (ref "C214") (pin "2") (pinfunction "2_2") (pintype "passive"))
      (node (ref "C215") (pin "2") (pinfunction "2_2") (pintype "passive"))
      (node (ref "C216") (pin "2") (pinfunction "2_2") (pintype "passive"))
      (node (ref "C217") (pin "2") (pinfunction "2_2") (pintype "passive"))
      (node (ref "C218") (pin "2") (pinfunction "2_2") (pintype "passive"))
      (node (ref "C219") (pin "2") (pinfunction "2_2") (pintype "passive"))
      (node (ref "C220") (pin "2") (pinfunction "2_2") (pintype "passive"))
      (node (ref "C221") (pin "2") (pinfunction "2_2") (pintype "passive"))
      (node (ref "C222") (pin "2") (pinfunction "2_2") (pintype "passive"))
      (node (ref "C223") (pin "2") (pinfunction "2_2") (pintype "passive"))
      (node (ref "C224") (pin "2") (pinfunction "2_2") (pintype "passive"))
      (node (ref "C225") (pin "2") (pinfunction "2_2") (pintype "passive"))
      (node (ref "C226") (pin "2") (pinfunction "2_2") (pintype "passive"))
      (node (ref "C227") (pin "2") (pinfunction "2_2") (pintype "passive"))
      (node (ref "C228") (pin "2") (pinfunction "2_2") (pintype "passive"))
      (node (ref "C229") (pin "2") (pinfunction "2_2") (pintype "passive"))
      (node (ref "C230") (pin "2") (pinfunction "2_2") (pintype "passive"))
      (node (ref "C231") (pin "2") (pinfunction "2_2") (pintype "passive"))
      (node (ref "C232") (pin "2") (pinfunction "2_2") (pintype "passive"))
      (node (ref "C233") (pin "2") (pinfunction "2_2") (pintype "passive"))
      (node (ref "C234") (pin "2") (pinfunction "2_2") (pintype "passive"))
      (node (ref "C235") (pin "2") (pinfunction "2_2") (pintype "passive"))
      (node (ref "C237") (pin "2") (pinfunction "2_2") (pintype "passive"))
      (node (ref "C238") (pin "2") (pinfunction "2_2") (pintype "passive"))
      (node (ref "C239") (pin "2") (pinfunction "2_2") (pintype "passive"))
      (node (ref "C240") (pin "2") (pinfunction "2_2") (pintype "passive"))
      (node (ref "C241") (pin "2") (pinfunction "2_2") (pintype "passive"))
      (node (ref "C242") (pin "2") (pinfunction "2_2") (pintype "passive"))
      (node (ref "C243") (pin "2") (pinfunction "2_2") (pintype "passive"))
      (node (ref "C244") (pin "2") (pinfunction "2_2") (pintype "passive"))
      (node (ref "C245") (pin "2") (pinfunction "2_2") (pintype "passive"))
      (node (ref "C246") (pin "2") (pinfunction "2_2") (pintype "passive"))
      (node (ref "C247") (pin "2") (pinfunction "2_2") (pintype "passive"))
      (node (ref "C248") (pin "2") (pinfunction "2_2") (pintype "passive"))
      (node (ref "C249") (pin "2") (pinfunction "2_2") (pintype "passive"))
      (node (ref "C250") (pin "2") (pinfunction "2_2") (pintype "passive"))
      (node (ref "C251") (pin "2") (pinfunction "2_2") (pintype "passive"))
      (node (ref "C252") (pin "2") (pinfunction "2_2") (pintype "passive"))
      (node (ref "C253") (pin "2") (pinfunction "2_2") (pintype "passive"))
      (node (ref "C254") (pin "2") (pinfunction "2_2") (pintype "passive"))
      (node (ref "C255") (pin "2") (pinfunction "2_2") (pintype "passive"))
      (node (ref "C256") (pin "2") (pinfunction "2_2") (pintype "passive"))
      (node (ref "C257") (pin "2") (pinfunction "2_2") (pintype "passive"))
      (node (ref "C258") (pin "2") (pinfunction "2_2") (pintype "passive"))
      (node (ref "C259") (pin "2") (pinfunction "2_2") (pintype "passive"))
      (node (ref "C260") (pin "2") (pinfunction "2_2") (pintype "passive"))
      (node (ref "C261") (pin "2") (pinfunction "2_2") (pintype "passive"))
      (node (ref "C262") (pin "2") (pinfunction "2_2") (pintype "passive"))
      (node (ref "C263") (pin "2") (pinfunction "2_2") (pintype "passive"))
      (node (ref "C264") (pin "2") (pinfunction "2_2") (pintype "passive"))
      (node (ref "C265") (pin "2") (pinfunction "2_2") (pintype "passive"))
      (node (ref "C266") (pin "2") (pinfunction "2_2") (pintype "passive"))
      (node (ref "C36") (pin "2") (pinfunction "2_2") (pintype "passive"))
      (node (ref "U1") (pin "A11") (pinfunction "VDD_TOP_4_A11") (pintype "passive"))
      (node (ref "U1") (pin "AA10") (pinfunction "VDD_TOP_1_AA10") (pintype "passive"))
      (node (ref "U1") (pin "AA12") (pinfunction "VDD_TOP_1_AA12") (pintype "passive"))
      (node (ref "U1") (pin "AA14") (pinfunction "VDD_TOP_1_AA14") (pintype "passive"))
      (node (ref "U1") (pin "AA16") (pinfunction "VDD_TOP_1_AA16") (pintype "passive"))
      (node (ref "U1") (pin "AA18") (pinfunction "VDD_TOP_1_AA18") (pintype "passive"))
      (node (ref "U1") (pin "AA19") (pinfunction "VDD_TOP_2_AA19") (pintype "passive"))
      (node (ref "U1") (pin "AA21") (pinfunction "VDD_TOP_2_AA21") (pintype "passive"))
      (node (ref "U1") (pin "AA23") (pinfunction "VDD_TOP_2_AA23") (pintype "passive"))
      (node (ref "U1") (pin "AA25") (pinfunction "VDD_TOP_2_AA25") (pintype "passive"))
      (node (ref "U1") (pin "AA27") (pinfunction "VDD_TOP_2_AA27") (pintype "passive"))
      (node (ref "U1") (pin "AA29") (pinfunction "VDD_TOP_2_AA29") (pintype "passive"))
      (node (ref "U1") (pin "AA31") (pinfunction "VDD_TOP_2_AA31") (pintype "passive"))
      (node (ref "U1") (pin "AA6") (pinfunction "VDD_TOP_1_AA6") (pintype "passive"))
      (node (ref "U1") (pin "AA8") (pinfunction "VDD_TOP_1_AA8") (pintype "passive"))
      (node (ref "U1") (pin "AB11") (pinfunction "VDD_TOP_1_AB11") (pintype "passive"))
      (node (ref "U1") (pin "AB13") (pinfunction "VDD_TOP_1_AB13") (pintype "passive"))
      (node (ref "U1") (pin "AB15") (pinfunction "VDD_TOP_1_AB15") (pintype "passive"))
      (node (ref "U1") (pin "AB17") (pinfunction "VDD_TOP_1_AB17") (pintype "passive"))
      (node (ref "U1") (pin "AB20") (pinfunction "VDD_TOP_2_AB20") (pintype "passive"))
      (node (ref "U1") (pin "AB22") (pinfunction "VDD_TOP_2_AB22") (pintype "passive"))
      (node (ref "U1") (pin "AB24") (pinfunction "VDD_TOP_2_AB24") (pintype "passive"))
      (node (ref "U1") (pin "AB26") (pinfunction "VDD_TOP_2_AB26") (pintype "passive"))
      (node (ref "U1") (pin "AB28") (pinfunction "VDD_TOP_2_AB28") (pintype "passive"))
      (node (ref "U1") (pin "AB30") (pinfunction "VDD_TOP_2_AB30") (pintype "passive"))
      (node (ref "U1") (pin "AB32") (pinfunction "VDD_TOP_2_AB32") (pintype "passive"))
      (node (ref "U1") (pin "AB7") (pinfunction "VDD_TOP_1_AB7") (pintype "passive"))
      (node (ref "U1") (pin "AB9") (pinfunction "VDD_TOP_1_AB9") (pintype "passive"))
      (node (ref "U1") (pin "AC10") (pinfunction "VDD_TOP_1_AC10") (pintype "passive"))
      (node (ref "U1") (pin "AC12") (pinfunction "VDD_TOP_1_AC12") (pintype "passive"))
      (node (ref "U1") (pin "AC14") (pinfunction "VDD_TOP_1_AC14") (pintype "passive"))
      (node (ref "U1") (pin "AC16") (pinfunction "VDD_TOP_1_AC16") (pintype "passive"))
      (node (ref "U1") (pin "AC18") (pinfunction "VDD_TOP_1_AC18") (pintype "passive"))
      (node (ref "U1") (pin "AC19") (pinfunction "VDD_TOP_2_AC19") (pintype "passive"))
      (node (ref "U1") (pin "AC21") (pinfunction "VDD_TOP_2_AC21") (pintype "passive"))
      (node (ref "U1") (pin "AC23") (pinfunction "VDD_TOP_2_AC23") (pintype "passive"))
      (node (ref "U1") (pin "AC25") (pinfunction "VDD_TOP_2_AC25") (pintype "passive"))
      (node (ref "U1") (pin "AC27") (pinfunction "VDD_TOP_2_AC27") (pintype "passive"))
      (node (ref "U1") (pin "AC29") (pinfunction "VDD_TOP_2_AC29") (pintype "passive"))
      (node (ref "U1") (pin "AC31") (pinfunction "VDD_TOP_2_AC31") (pintype "passive"))
      (node (ref "U1") (pin "AC6") (pinfunction "VDD_TOP_1_AC6") (pintype "passive"))
      (node (ref "U1") (pin "AC8") (pinfunction "VDD_TOP_1_AC8") (pintype "passive"))
      (node (ref "U1") (pin "AD11") (pinfunction "VDD_TOP_1_AD11") (pintype "passive"))
      (node (ref "U1") (pin "AD13") (pinfunction "VDD_TOP_1_AD13") (pintype "passive"))
      (node (ref "U1") (pin "AD15") (pinfunction "VDD_TOP_1_AD15") (pintype "passive"))
      (node (ref "U1") (pin "AD17") (pinfunction "VDD_TOP_1_AD17") (pintype "passive"))
      (node (ref "U1") (pin "AD20") (pinfunction "VDD_TOP_2_AD20") (pintype "passive"))
      (node (ref "U1") (pin "AD22") (pinfunction "VDD_TOP_2_AD22") (pintype "passive"))
      (node (ref "U1") (pin "AD24") (pinfunction "VDD_TOP_2_AD24") (pintype "passive"))
      (node (ref "U1") (pin "AD26") (pinfunction "VDD_TOP_2_AD26") (pintype "passive"))
      (node (ref "U1") (pin "AD28") (pinfunction "VDD_TOP_2_AD28") (pintype "passive"))
      (node (ref "U1") (pin "AD30") (pinfunction "VDD_TOP_2_AD30") (pintype "passive"))
      (node (ref "U1") (pin "AD32") (pinfunction "VDD_TOP_2_AD32") (pintype "passive"))
      (node (ref "U1") (pin "AD5") (pinfunction "VDD_TOP_1_AD5") (pintype "passive"))
      (node (ref "U1") (pin "AD7") (pinfunction "VDD_TOP_1_AD7") (pintype "passive"))
      (node (ref "U1") (pin "AD9") (pinfunction "VDD_TOP_1_AD9") (pintype "passive"))
      (node (ref "U1") (pin "AE10") (pinfunction "VDD_TOP_1_AE10") (pintype "passive"))
      (node (ref "U1") (pin "AE12") (pinfunction "VDD_TOP_1_AE12") (pintype "passive"))
      (node (ref "U1") (pin "AE14") (pinfunction "VDD_TOP_1_AE14") (pintype "passive"))
      (node (ref "U1") (pin "AE16") (pinfunction "VDD_TOP_1_AE16") (pintype "passive"))
      (node (ref "U1") (pin "AE18") (pinfunction "VDD_TOP_1_AE18") (pintype "passive"))
      (node (ref "U1") (pin "AE19") (pinfunction "VDD_TOP_2_AE19") (pintype "passive"))
      (node (ref "U1") (pin "AE21") (pinfunction "VDD_TOP_2_AE21") (pintype "passive"))
      (node (ref "U1") (pin "AE23") (pinfunction "VDD_TOP_2_AE23") (pintype "passive"))
      (node (ref "U1") (pin "AE25") (pinfunction "VDD_TOP_2_AE25") (pintype "passive"))
      (node (ref "U1") (pin "AE27") (pinfunction "VDD_TOP_2_AE27") (pintype "passive"))
      (node (ref "U1") (pin "AE29") (pinfunction "VDD_TOP_2_AE29") (pintype "passive"))
      (node (ref "U1") (pin "AE31") (pinfunction "VDD_TOP_2_AE31") (pintype "passive"))
      (node (ref "U1") (pin "AE6") (pinfunction "VDD_TOP_1_AE6") (pintype "passive"))
      (node (ref "U1") (pin "AE8") (pinfunction "VDD_TOP_1_AE8") (pintype "passive"))
      (node (ref "U1") (pin "AF1") (pinfunction "VDD_TOP_1_AF1") (pintype "passive"))
      (node (ref "U1") (pin "AF11") (pinfunction "VDD_TOP_1_AF11") (pintype "passive"))
      (node (ref "U1") (pin "AF13") (pinfunction "VDD_TOP_1_AF13") (pintype "passive"))
      (node (ref "U1") (pin "AF15") (pinfunction "VDD_TOP_1_AF15") (pintype "passive"))
      (node (ref "U1") (pin "AF17") (pinfunction "VDD_TOP_1_AF17") (pintype "passive"))
      (node (ref "U1") (pin "AF20") (pinfunction "VDD_TOP_2_AF20") (pintype "passive"))
      (node (ref "U1") (pin "AF22") (pinfunction "VDD_TOP_2_AF22") (pintype "passive"))
      (node (ref "U1") (pin "AF24") (pinfunction "VDD_TOP_2_AF24") (pintype "passive"))
      (node (ref "U1") (pin "AF26") (pinfunction "VDD_TOP_2_AF26") (pintype "passive"))
      (node (ref "U1") (pin "AF28") (pinfunction "VDD_TOP_2_AF28") (pintype "passive"))
      (node (ref "U1") (pin "AF30") (pinfunction "VDD_TOP_2_AF30") (pintype "passive"))
      (node (ref "U1") (pin "AF32") (pinfunction "VDD_TOP_2_AF32") (pintype "passive"))
      (node (ref "U1") (pin "AF7") (pinfunction "VDD_TOP_1_AF7") (pintype "passive"))
      (node (ref "U1") (pin "AF9") (pinfunction "VDD_TOP_1_AF9") (pintype "passive"))
      (node (ref "U1") (pin "AG10") (pinfunction "VDD_TOP_1_AG10") (pintype "passive"))
      (node (ref "U1") (pin "AG12") (pinfunction "VDD_TOP_1_AG12") (pintype "passive"))
      (node (ref "U1") (pin "AG14") (pinfunction "VDD_TOP_1_AG14") (pintype "passive"))
      (node (ref "U1") (pin "AG16") (pinfunction "VDD_TOP_1_AG16") (pintype "passive"))
      (node (ref "U1") (pin "AG18") (pinfunction "VDD_TOP_1_AG18") (pintype "passive"))
      (node (ref "U1") (pin "AG19") (pinfunction "VDD_TOP_2_AG19") (pintype "passive"))
      (node (ref "U1") (pin "AG21") (pinfunction "VDD_TOP_2_AG21") (pintype "passive"))
      (node (ref "U1") (pin "AG23") (pinfunction "VDD_TOP_2_AG23") (pintype "passive"))
      (node (ref "U1") (pin "AG25") (pinfunction "VDD_TOP_2_AG25") (pintype "passive"))
      (node (ref "U1") (pin "AG27") (pinfunction "VDD_TOP_2_AG27") (pintype "passive"))
      (node (ref "U1") (pin "AG29") (pinfunction "VDD_TOP_2_AG29") (pintype "passive"))
      (node (ref "U1") (pin "AG31") (pinfunction "VDD_TOP_2_AG31") (pintype "passive"))
      (node (ref "U1") (pin "AG6") (pinfunction "VDD_TOP_1_AG6") (pintype "passive"))
      (node (ref "U1") (pin "AG8") (pinfunction "VDD_TOP_1_AG8") (pintype "passive"))
      (node (ref "U1") (pin "AH11") (pinfunction "VDD_TOP_1_AH11") (pintype "passive"))
      (node (ref "U1") (pin "AH13") (pinfunction "VDD_TOP_1_AH13") (pintype "passive"))
      (node (ref "U1") (pin "AH15") (pinfunction "VDD_TOP_1_AH15") (pintype "passive"))
      (node (ref "U1") (pin "AH17") (pinfunction "VDD_TOP_1_AH17") (pintype "passive"))
      (node (ref "U1") (pin "AH20") (pinfunction "VDD_TOP_2_AH20") (pintype "passive"))
      (node (ref "U1") (pin "AH22") (pinfunction "VDD_TOP_2_AH22") (pintype "passive"))
      (node (ref "U1") (pin "AH24") (pinfunction "VDD_TOP_2_AH24") (pintype "passive"))
      (node (ref "U1") (pin "AH26") (pinfunction "VDD_TOP_2_AH26") (pintype "passive"))
      (node (ref "U1") (pin "AH28") (pinfunction "VDD_TOP_2_AH28") (pintype "passive"))
      (node (ref "U1") (pin "AH30") (pinfunction "VDD_TOP_2_AH30") (pintype "passive"))
      (node (ref "U1") (pin "AH32") (pinfunction "VDD_TOP_2_AH32") (pintype "passive"))
      (node (ref "U1") (pin "AH5") (pinfunction "VDD_TOP_1_AH5") (pintype "passive"))
      (node (ref "U1") (pin "AH7") (pinfunction "VDD_TOP_1_AH7") (pintype "passive"))
      (node (ref "U1") (pin "AH9") (pinfunction "VDD_TOP_1_AH9") (pintype "passive"))
      (node (ref "U1") (pin "AJ10") (pinfunction "VDD_TOP_1_AJ10") (pintype "passive"))
      (node (ref "U1") (pin "AJ12") (pinfunction "VDD_TOP_1_AJ12") (pintype "passive"))
      (node (ref "U1") (pin "AJ14") (pinfunction "VDD_TOP_1_AJ14") (pintype "passive"))
      (node (ref "U1") (pin "AJ16") (pinfunction "VDD_TOP_1_AJ16") (pintype "passive"))
      (node (ref "U1") (pin "AJ18") (pinfunction "VDD_TOP_1_AJ18") (pintype "passive"))
      (node (ref "U1") (pin "AJ19") (pinfunction "VDD_TOP_2_AJ19") (pintype "passive"))
      (node (ref "U1") (pin "AJ21") (pinfunction "VDD_TOP_2_AJ21") (pintype "passive"))
      (node (ref "U1") (pin "AJ23") (pinfunction "VDD_TOP_2_AJ23") (pintype "passive"))
      (node (ref "U1") (pin "AJ25") (pinfunction "VDD_TOP_2_AJ25") (pintype "passive"))
      (node (ref "U1") (pin "AJ27") (pinfunction "VDD_TOP_2_AJ27") (pintype "passive"))
      (node (ref "U1") (pin "AJ29") (pinfunction "VDD_TOP_2_AJ29") (pintype "passive"))
      (node (ref "U1") (pin "AJ31") (pinfunction "VDD_TOP_2_AJ31") (pintype "passive"))
      (node (ref "U1") (pin "AJ6") (pinfunction "VDD_TOP_1_AJ6") (pintype "passive"))
      (node (ref "U1") (pin "AJ8") (pinfunction "VDD_TOP_1_AJ8") (pintype "passive"))
      (node (ref "U1") (pin "AK11") (pinfunction "VDD_TOP_1_AK11") (pintype "passive"))
      (node (ref "U1") (pin "AK13") (pinfunction "VDD_TOP_1_AK13") (pintype "passive"))
      (node (ref "U1") (pin "AK15") (pinfunction "VDD_TOP_1_AK15") (pintype "passive"))
      (node (ref "U1") (pin "AK17") (pinfunction "VDD_TOP_1_AK17") (pintype "passive"))
      (node (ref "U1") (pin "AK20") (pinfunction "VDD_TOP_2_AK20") (pintype "passive"))
      (node (ref "U1") (pin "AK22") (pinfunction "VDD_TOP_2_AK22") (pintype "passive"))
      (node (ref "U1") (pin "AK24") (pinfunction "VDD_TOP_2_AK24") (pintype "passive"))
      (node (ref "U1") (pin "AK26") (pinfunction "VDD_TOP_2_AK26") (pintype "passive"))
      (node (ref "U1") (pin "AK28") (pinfunction "VDD_TOP_2_AK28") (pintype "passive"))
      (node (ref "U1") (pin "AK30") (pinfunction "VDD_TOP_2_AK30") (pintype "passive"))
      (node (ref "U1") (pin "AK5") (pinfunction "VDD_TOP_1_AK5") (pintype "passive"))
      (node (ref "U1") (pin "AK7") (pinfunction "VDD_TOP_1_AK7") (pintype "passive"))
      (node (ref "U1") (pin "AK9") (pinfunction "VDD_TOP_1_AK9") (pintype "passive"))
      (node (ref "U1") (pin "AL10") (pinfunction "VDD_TOP_1_AL10") (pintype "passive"))
      (node (ref "U1") (pin "AL12") (pinfunction "VDD_TOP_1_AL12") (pintype "passive"))
      (node (ref "U1") (pin "AL14") (pinfunction "VDD_TOP_1_AL14") (pintype "passive"))
      (node (ref "U1") (pin "AL16") (pinfunction "VDD_TOP_1_AL16") (pintype "passive"))
      (node (ref "U1") (pin "AL18") (pinfunction "VDD_TOP_1_AL18") (pintype "passive"))
      (node (ref "U1") (pin "AL19") (pinfunction "VDD_TOP_2_AL19") (pintype "passive"))
      (node (ref "U1") (pin "AL21") (pinfunction "VDD_TOP_2_AL21") (pintype "passive"))
      (node (ref "U1") (pin "AL23") (pinfunction "VDD_TOP_2_AL23") (pintype "passive"))
      (node (ref "U1") (pin "AL25") (pinfunction "VDD_TOP_2_AL25") (pintype "passive"))
      (node (ref "U1") (pin "AL27") (pinfunction "VDD_TOP_2_AL27") (pintype "passive"))
      (node (ref "U1") (pin "AL29") (pinfunction "VDD_TOP_2_AL29") (pintype "passive"))
      (node (ref "U1") (pin "AL31") (pinfunction "VDD_TOP_2_AL31") (pintype "passive"))
      (node (ref "U1") (pin "AL6") (pinfunction "VDD_TOP_1_AL6") (pintype "passive"))
      (node (ref "U1") (pin "AL8") (pinfunction "VDD_TOP_1_AL8") (pintype "passive"))
      (node (ref "U1") (pin "AM11") (pinfunction "VDD_TOP_1_AM11") (pintype "passive"))
      (node (ref "U1") (pin "AM13") (pinfunction "VDD_TOP_1_AM13") (pintype "passive"))
      (node (ref "U1") (pin "AM15") (pinfunction "VDD_TOP_1_AM15") (pintype "passive"))
      (node (ref "U1") (pin "AM17") (pinfunction "VDD_TOP_1_AM17") (pintype "passive"))
      (node (ref "U1") (pin "AM24") (pinfunction "VDD_TOP_2_AM24") (pintype "passive"))
      (node (ref "U1") (pin "AM28") (pinfunction "VDD_TOP_2_AM28") (pintype "passive"))
      (node (ref "U1") (pin "AM30") (pinfunction "VDD_TOP_2_AM30") (pintype "passive"))
      (node (ref "U1") (pin "AM9") (pinfunction "VDD_TOP_1_AM9") (pintype "passive"))
      (node (ref "U1") (pin "AN18") (pinfunction "VDD_TOP_1_AN18") (pintype "passive"))
      (node (ref "U1") (pin "AT26") (pinfunction "VDD_TOP_2_AT26") (pintype "passive"))
      (node (ref "U1") (pin "D19") (pinfunction "VDD_TOP_3_D19") (pintype "passive"))
      (node (ref "U1") (pin "E13") (pinfunction "VDD_TOP_4_E13") (pintype "passive"))
      (node (ref "U1") (pin "E20") (pinfunction "VDD_TOP_3_E20") (pintype "passive"))
      (node (ref "U1") (pin "E22") (pinfunction "VDD_TOP_3_E22") (pintype "passive"))
      (node (ref "U1") (pin "E24") (pinfunction "VDD_TOP_3_E24") (pintype "passive"))
      (node (ref "U1") (pin "E26") (pinfunction "VDD_TOP_3_E26") (pintype "passive"))
      (node (ref "U1") (pin "E28") (pinfunction "VDD_TOP_3_E28") (pintype "passive"))
      (node (ref "U1") (pin "E7") (pinfunction "VDD_TOP_4_E7") (pintype "passive"))
      (node (ref "U1") (pin "E9") (pinfunction "VDD_TOP_4_E9") (pintype "passive"))
      (node (ref "U1") (pin "F10") (pinfunction "VDD_TOP_4_F10") (pintype "passive"))
      (node (ref "U1") (pin "F12") (pinfunction "VDD_TOP_4_F12") (pintype "passive"))
      (node (ref "U1") (pin "F14") (pinfunction "VDD_TOP_4_F14") (pintype "passive"))
      (node (ref "U1") (pin "F16") (pinfunction "VDD_TOP_4_F16") (pintype "passive"))
      (node (ref "U1") (pin "F18") (pinfunction "VDD_TOP_4_F18") (pintype "passive"))
      (node (ref "U1") (pin "F19") (pinfunction "VDD_TOP_3_F19") (pintype "passive"))
      (node (ref "U1") (pin "F21") (pinfunction "VDD_TOP_3_F21") (pintype "passive"))
      (node (ref "U1") (pin "F23") (pinfunction "VDD_TOP_3_F23") (pintype "passive"))
      (node (ref "U1") (pin "F25") (pinfunction "VDD_TOP_3_F25") (pintype "passive"))
      (node (ref "U1") (pin "F27") (pinfunction "VDD_TOP_3_F27") (pintype "passive"))
      (node (ref "U1") (pin "F29") (pinfunction "VDD_TOP_3_F29") (pintype "passive"))
      (node (ref "U1") (pin "F31") (pinfunction "VDD_TOP_3_F31") (pintype "passive"))
      (node (ref "U1") (pin "F6") (pinfunction "VDD_TOP_4_F6") (pintype "passive"))
      (node (ref "U1") (pin "F8") (pinfunction "VDD_TOP_4_F8") (pintype "passive"))
      (node (ref "U1") (pin "G11") (pinfunction "VDD_TOP_4_G11") (pintype "passive"))
      (node (ref "U1") (pin "G13") (pinfunction "VDD_TOP_4_G13") (pintype "passive"))
      (node (ref "U1") (pin "G15") (pinfunction "VDD_TOP_4_G15") (pintype "passive"))
      (node (ref "U1") (pin "G17") (pinfunction "VDD_TOP_4_G17") (pintype "passive"))
      (node (ref "U1") (pin "G20") (pinfunction "VDD_TOP_3_G20") (pintype "passive"))
      (node (ref "U1") (pin "G22") (pinfunction "VDD_TOP_3_G22") (pintype "passive"))
      (node (ref "U1") (pin "G24") (pinfunction "VDD_TOP_3_G24") (pintype "passive"))
      (node (ref "U1") (pin "G26") (pinfunction "VDD_TOP_3_G26") (pintype "passive"))
      (node (ref "U1") (pin "G28") (pinfunction "VDD_TOP_3_G28") (pintype "passive"))
      (node (ref "U1") (pin "G30") (pinfunction "VDD_TOP_3_G30") (pintype "passive"))
      (node (ref "U1") (pin "G32") (pinfunction "VDD_TOP_3_G32") (pintype "passive"))
      (node (ref "U1") (pin "G7") (pinfunction "VDD_TOP_4_G7") (pintype "passive"))
      (node (ref "U1") (pin "G9") (pinfunction "VDD_TOP_4_G9") (pintype "passive"))
      (node (ref "U1") (pin "H10") (pinfunction "VDD_TOP_4_H10") (pintype "passive"))
      (node (ref "U1") (pin "H12") (pinfunction "VDD_TOP_4_H12") (pintype "passive"))
      (node (ref "U1") (pin "H14") (pinfunction "VDD_TOP_4_H14") (pintype "passive"))
      (node (ref "U1") (pin "H16") (pinfunction "VDD_TOP_4_H16") (pintype "passive"))
      (node (ref "U1") (pin "H18") (pinfunction "VDD_TOP_4_H18") (pintype "passive"))
      (node (ref "U1") (pin "H19") (pinfunction "VDD_TOP_3_H19") (pintype "passive"))
      (node (ref "U1") (pin "H21") (pinfunction "VDD_TOP_3_H21") (pintype "passive"))
      (node (ref "U1") (pin "H23") (pinfunction "VDD_TOP_3_H23") (pintype "passive"))
      (node (ref "U1") (pin "H25") (pinfunction "VDD_TOP_3_H25") (pintype "passive"))
      (node (ref "U1") (pin "H27") (pinfunction "VDD_TOP_3_H27") (pintype "passive"))
      (node (ref "U1") (pin "H29") (pinfunction "VDD_TOP_3_H29") (pintype "passive"))
      (node (ref "U1") (pin "H31") (pinfunction "VDD_TOP_3_H31") (pintype "passive"))
      (node (ref "U1") (pin "H6") (pinfunction "VDD_TOP_4_H6") (pintype "passive"))
      (node (ref "U1") (pin "H8") (pinfunction "VDD_TOP_4_H8") (pintype "passive"))
      (node (ref "U1") (pin "J11") (pinfunction "VDD_TOP_4_J11") (pintype "passive"))
      (node (ref "U1") (pin "J13") (pinfunction "VDD_TOP_4_J13") (pintype "passive"))
      (node (ref "U1") (pin "J15") (pinfunction "VDD_TOP_4_J15") (pintype "passive"))
      (node (ref "U1") (pin "J17") (pinfunction "VDD_TOP_4_J17") (pintype "passive"))
      (node (ref "U1") (pin "J20") (pinfunction "VDD_TOP_3_J20") (pintype "passive"))
      (node (ref "U1") (pin "J22") (pinfunction "VDD_TOP_3_J22") (pintype "passive"))
      (node (ref "U1") (pin "J24") (pinfunction "VDD_TOP_3_J24") (pintype "passive"))
      (node (ref "U1") (pin "J26") (pinfunction "VDD_TOP_3_J26") (pintype "passive"))
      (node (ref "U1") (pin "J28") (pinfunction "VDD_TOP_3_J28") (pintype "passive"))
      (node (ref "U1") (pin "J30") (pinfunction "VDD_TOP_3_J30") (pintype "passive"))
      (node (ref "U1") (pin "J32") (pinfunction "VDD_TOP_3_J32") (pintype "passive"))
      (node (ref "U1") (pin "J5") (pinfunction "VDD_TOP_4_J5") (pintype "passive"))
      (node (ref "U1") (pin "J7") (pinfunction "VDD_TOP_4_J7") (pintype "passive"))
      (node (ref "U1") (pin "J9") (pinfunction "VDD_TOP_4_J9") (pintype "passive"))
      (node (ref "U1") (pin "K10") (pinfunction "VDD_TOP_4_K10") (pintype "passive"))
      (node (ref "U1") (pin "K12") (pinfunction "VDD_TOP_4_K12") (pintype "passive"))
      (node (ref "U1") (pin "K14") (pinfunction "VDD_TOP_4_K14") (pintype "passive"))
      (node (ref "U1") (pin "K16") (pinfunction "VDD_TOP_4_K16") (pintype "passive"))
      (node (ref "U1") (pin "K18") (pinfunction "VDD_TOP_4_K18") (pintype "passive"))
      (node (ref "U1") (pin "K19") (pinfunction "VDD_TOP_3_K19") (pintype "passive"))
      (node (ref "U1") (pin "K21") (pinfunction "VDD_TOP_3_K21") (pintype "passive"))
      (node (ref "U1") (pin "K23") (pinfunction "VDD_TOP_3_K23") (pintype "passive"))
      (node (ref "U1") (pin "K25") (pinfunction "VDD_TOP_3_K25") (pintype "passive"))
      (node (ref "U1") (pin "K27") (pinfunction "VDD_TOP_3_K27") (pintype "passive"))
      (node (ref "U1") (pin "K29") (pinfunction "VDD_TOP_3_K29") (pintype "passive"))
      (node (ref "U1") (pin "K31") (pinfunction "VDD_TOP_3_K31") (pintype "passive"))
      (node (ref "U1") (pin "K6") (pinfunction "VDD_TOP_4_K6") (pintype "passive"))
      (node (ref "U1") (pin "K8") (pinfunction "VDD_TOP_4_K8") (pintype "passive"))
      (node (ref "U1") (pin "L11") (pinfunction "VDD_TOP_4_L11") (pintype "passive"))
      (node (ref "U1") (pin "L13") (pinfunction "VDD_TOP_4_L13") (pintype "passive"))
      (node (ref "U1") (pin "L15") (pinfunction "VDD_TOP_4_L15") (pintype "passive"))
      (node (ref "U1") (pin "L17") (pinfunction "VDD_TOP_4_L17") (pintype "passive"))
      (node (ref "U1") (pin "L20") (pinfunction "VDD_TOP_3_L20") (pintype "passive"))
      (node (ref "U1") (pin "L22") (pinfunction "VDD_TOP_3_L22") (pintype "passive"))
      (node (ref "U1") (pin "L24") (pinfunction "VDD_TOP_3_L24") (pintype "passive"))
      (node (ref "U1") (pin "L26") (pinfunction "VDD_TOP_3_L26") (pintype "passive"))
      (node (ref "U1") (pin "L28") (pinfunction "VDD_TOP_3_L28") (pintype "passive"))
      (node (ref "U1") (pin "L30") (pinfunction "VDD_TOP_3_L30") (pintype "passive"))
      (node (ref "U1") (pin "L36") (pinfunction "VDD_TOP_3_L36") (pintype "passive"))
      (node (ref "U1") (pin "L5") (pinfunction "VDD_TOP_4_L5") (pintype "passive"))
      (node (ref "U1") (pin "L7") (pinfunction "VDD_TOP_4_L7") (pintype "passive"))
      (node (ref "U1") (pin "L9") (pinfunction "VDD_TOP_4_L9") (pintype "passive"))
      (node (ref "U1") (pin "M10") (pinfunction "VDD_TOP_4_M10") (pintype "passive"))
      (node (ref "U1") (pin "M12") (pinfunction "VDD_TOP_4_M12") (pintype "passive"))
      (node (ref "U1") (pin "M14") (pinfunction "VDD_TOP_4_M14") (pintype "passive"))
      (node (ref "U1") (pin "M16") (pinfunction "VDD_TOP_4_M16") (pintype "passive"))
      (node (ref "U1") (pin "M18") (pinfunction "VDD_TOP_4_M18") (pintype "passive"))
      (node (ref "U1") (pin "M19") (pinfunction "VDD_TOP_3_M19") (pintype "passive"))
      (node (ref "U1") (pin "M21") (pinfunction "VDD_TOP_3_M21") (pintype "passive"))
      (node (ref "U1") (pin "M23") (pinfunction "VDD_TOP_3_M23") (pintype "passive"))
      (node (ref "U1") (pin "M25") (pinfunction "VDD_TOP_3_M25") (pintype "passive"))
      (node (ref "U1") (pin "M27") (pinfunction "VDD_TOP_3_M27") (pintype "passive"))
      (node (ref "U1") (pin "M29") (pinfunction "VDD_TOP_3_M29") (pintype "passive"))
      (node (ref "U1") (pin "M31") (pinfunction "VDD_TOP_3_M31") (pintype "passive"))
      (node (ref "U1") (pin "M6") (pinfunction "VDD_TOP_4_M6") (pintype "passive"))
      (node (ref "U1") (pin "M8") (pinfunction "VDD_TOP_4_M8") (pintype "passive"))
      (node (ref "U1") (pin "N11") (pinfunction "VDD_TOP_4_N11") (pintype "passive"))
      (node (ref "U1") (pin "N13") (pinfunction "VDD_TOP_4_N13") (pintype "passive"))
      (node (ref "U1") (pin "N15") (pinfunction "VDD_TOP_4_N15") (pintype "passive"))
      (node (ref "U1") (pin "N17") (pinfunction "VDD_TOP_4_N17") (pintype "passive"))
      (node (ref "U1") (pin "N20") (pinfunction "VDD_TOP_3_N20") (pintype "passive"))
      (node (ref "U1") (pin "N22") (pinfunction "VDD_TOP_3_N22") (pintype "passive"))
      (node (ref "U1") (pin "N24") (pinfunction "VDD_TOP_3_N24") (pintype "passive"))
      (node (ref "U1") (pin "N26") (pinfunction "VDD_TOP_3_N26") (pintype "passive"))
      (node (ref "U1") (pin "N28") (pinfunction "VDD_TOP_3_N28") (pintype "passive"))
      (node (ref "U1") (pin "N30") (pinfunction "VDD_TOP_3_N30") (pintype "passive"))
      (node (ref "U1") (pin "N32") (pinfunction "VDD_TOP_3_N32") (pintype "passive"))
      (node (ref "U1") (pin "N5") (pinfunction "VDD_TOP_4_N5") (pintype "passive"))
      (node (ref "U1") (pin "N7") (pinfunction "VDD_TOP_4_N7") (pintype "passive"))
      (node (ref "U1") (pin "N9") (pinfunction "VDD_TOP_4_N9") (pintype "passive"))
      (node (ref "U1") (pin "P10") (pinfunction "VDD_TOP_4_P10") (pintype "passive"))
      (node (ref "U1") (pin "P12") (pinfunction "VDD_TOP_4_P12") (pintype "passive"))
      (node (ref "U1") (pin "P14") (pinfunction "VDD_TOP_4_P14") (pintype "passive"))
      (node (ref "U1") (pin "P16") (pinfunction "VDD_TOP_4_P16") (pintype "passive"))
      (node (ref "U1") (pin "P18") (pinfunction "VDD_TOP_4_P18") (pintype "passive"))
      (node (ref "U1") (pin "P19") (pinfunction "VDD_TOP_3_P19") (pintype "passive"))
      (node (ref "U1") (pin "P21") (pinfunction "VDD_TOP_3_P21") (pintype "passive"))
      (node (ref "U1") (pin "P23") (pinfunction "VDD_TOP_3_P23") (pintype "passive"))
      (node (ref "U1") (pin "P25") (pinfunction "VDD_TOP_3_P25") (pintype "passive"))
      (node (ref "U1") (pin "P27") (pinfunction "VDD_TOP_3_P27") (pintype "passive"))
      (node (ref "U1") (pin "P29") (pinfunction "VDD_TOP_3_P29") (pintype "passive"))
      (node (ref "U1") (pin "P31") (pinfunction "VDD_TOP_3_P31") (pintype "passive"))
      (node (ref "U1") (pin "P6") (pinfunction "VDD_TOP_4_P6") (pintype "passive"))
      (node (ref "U1") (pin "P8") (pinfunction "VDD_TOP_4_P8") (pintype "passive"))
      (node (ref "U1") (pin "R11") (pinfunction "VDD_TOP_4_R11") (pintype "passive"))
      (node (ref "U1") (pin "R13") (pinfunction "VDD_TOP_4_R13") (pintype "passive"))
      (node (ref "U1") (pin "R15") (pinfunction "VDD_TOP_4_R15") (pintype "passive"))
      (node (ref "U1") (pin "R17") (pinfunction "VDD_TOP_4_R17") (pintype "passive"))
      (node (ref "U1") (pin "R20") (pinfunction "VDD_TOP_3_R20") (pintype "passive"))
      (node (ref "U1") (pin "R22") (pinfunction "VDD_TOP_3_R22") (pintype "passive"))
      (node (ref "U1") (pin "R24") (pinfunction "VDD_TOP_3_R24") (pintype "passive"))
      (node (ref "U1") (pin "R26") (pinfunction "VDD_TOP_3_R26") (pintype "passive"))
      (node (ref "U1") (pin "R28") (pinfunction "VDD_TOP_3_R28") (pintype "passive"))
      (node (ref "U1") (pin "R30") (pinfunction "VDD_TOP_3_R30") (pintype "passive"))
      (node (ref "U1") (pin "R5") (pinfunction "VDD_TOP_4_R5") (pintype "passive"))
      (node (ref "U1") (pin "R7") (pinfunction "VDD_TOP_4_R7") (pintype "passive"))
      (node (ref "U1") (pin "R9") (pinfunction "VDD_TOP_4_R9") (pintype "passive"))
      (node (ref "U1") (pin "T10") (pinfunction "VDD_TOP_4_T10") (pintype "passive"))
      (node (ref "U1") (pin "T12") (pinfunction "VDD_TOP_4_T12") (pintype "passive"))
      (node (ref "U1") (pin "T14") (pinfunction "VDD_TOP_4_T14") (pintype "passive"))
      (node (ref "U1") (pin "T16") (pinfunction "VDD_TOP_4_T16") (pintype "passive"))
      (node (ref "U1") (pin "T18") (pinfunction "VDD_TOP_4_T18") (pintype "passive"))
      (node (ref "U1") (pin "T19") (pinfunction "VDD_TOP_3_T19") (pintype "passive"))
      (node (ref "U1") (pin "T21") (pinfunction "VDD_TOP_3_T21") (pintype "passive"))
      (node (ref "U1") (pin "T23") (pinfunction "VDD_TOP_3_T23") (pintype "passive"))
      (node (ref "U1") (pin "T25") (pinfunction "VDD_TOP_3_T25") (pintype "passive"))
      (node (ref "U1") (pin "T27") (pinfunction "VDD_TOP_3_T27") (pintype "passive"))
      (node (ref "U1") (pin "T29") (pinfunction "VDD_TOP_3_T29") (pintype "passive"))
      (node (ref "U1") (pin "T31") (pinfunction "VDD_TOP_3_T31") (pintype "passive"))
      (node (ref "U1") (pin "T6") (pinfunction "VDD_TOP_4_T6") (pintype "passive"))
      (node (ref "U1") (pin "T8") (pinfunction "VDD_TOP_4_T8") (pintype "passive"))
      (node (ref "U1") (pin "U11") (pinfunction "VDD_TOP_4_U11") (pintype "passive"))
      (node (ref "U1") (pin "U13") (pinfunction "VDD_TOP_4_U13") (pintype "passive"))
      (node (ref "U1") (pin "U15") (pinfunction "VDD_TOP_4_U15") (pintype "passive"))
      (node (ref "U1") (pin "U17") (pinfunction "VDD_TOP_4_U17") (pintype "passive"))
      (node (ref "U1") (pin "U20") (pinfunction "VDD_TOP_3_U20") (pintype "passive"))
      (node (ref "U1") (pin "U22") (pinfunction "VDD_TOP_3_U22") (pintype "passive"))
      (node (ref "U1") (pin "U24") (pinfunction "VDD_TOP_3_U24") (pintype "passive"))
      (node (ref "U1") (pin "U26") (pinfunction "VDD_TOP_3_U26") (pintype "passive"))
      (node (ref "U1") (pin "U28") (pinfunction "VDD_TOP_3_U28") (pintype "passive"))
      (node (ref "U1") (pin "U30") (pinfunction "VDD_TOP_3_U30") (pintype "passive"))
      (node (ref "U1") (pin "U5") (pinfunction "VDD_TOP_4_U5") (pintype "passive"))
      (node (ref "U1") (pin "U7") (pinfunction "VDD_TOP_4_U7") (pintype "passive"))
      (node (ref "U1") (pin "U9") (pinfunction "VDD_TOP_4_U9") (pintype "passive"))
      (node (ref "U1") (pin "V10") (pinfunction "VDD_TOP_4_V10") (pintype "passive"))
      (node (ref "U1") (pin "V12") (pinfunction "VDD_TOP_4_V12") (pintype "passive"))
      (node (ref "U1") (pin "V14") (pinfunction "VDD_TOP_4_V14") (pintype "passive"))
      (node (ref "U1") (pin "V16") (pinfunction "VDD_TOP_4_V16") (pintype "passive"))
      (node (ref "U1") (pin "V18") (pinfunction "VDD_TOP_4_V18") (pintype "passive"))
      (node (ref "U1") (pin "V19") (pinfunction "VDD_TOP_3_V19") (pintype "passive"))
      (node (ref "U1") (pin "V21") (pinfunction "VDD_TOP_3_V21") (pintype "passive"))
      (node (ref "U1") (pin "V23") (pinfunction "VDD_TOP_3_V23") (pintype "passive"))
      (node (ref "U1") (pin "V25") (pinfunction "VDD_TOP_3_V25") (pintype "passive"))
      (node (ref "U1") (pin "V27") (pinfunction "VDD_TOP_3_V27") (pintype "passive"))
      (node (ref "U1") (pin "V29") (pinfunction "VDD_TOP_3_V29") (pintype "passive"))
      (node (ref "U1") (pin "V31") (pinfunction "VDD_TOP_3_V31") (pintype "passive"))
      (node (ref "U1") (pin "V4") (pinfunction "VDD_TOP_4_V4") (pintype "passive"))
      (node (ref "U1") (pin "V6") (pinfunction "VDD_TOP_4_V6") (pintype "passive"))
      (node (ref "U1") (pin "V8") (pinfunction "VDD_TOP_4_V8") (pintype "passive"))
      (node (ref "U1") (pin "W10") (pinfunction "VDD_TOP_1_W10") (pintype "passive"))
      (node (ref "U1") (pin "W12") (pinfunction "VDD_TOP_1_W12") (pintype "passive"))
      (node (ref "U1") (pin "W14") (pinfunction "VDD_TOP_1_W14") (pintype "passive"))
      (node (ref "U1") (pin "W16") (pinfunction "VDD_TOP_1_W16") (pintype "passive"))
      (node (ref "U1") (pin "W18") (pinfunction "VDD_TOP_1_W18") (pintype "passive"))
      (node (ref "U1") (pin "W19") (pinfunction "VDD_TOP_2_W19") (pintype "passive"))
      (node (ref "U1") (pin "W21") (pinfunction "VDD_TOP_2_W21") (pintype "passive"))
      (node (ref "U1") (pin "W23") (pinfunction "VDD_TOP_2_W23") (pintype "passive"))
      (node (ref "U1") (pin "W25") (pinfunction "VDD_TOP_2_W25") (pintype "passive"))
      (node (ref "U1") (pin "W27") (pinfunction "VDD_TOP_2_W27") (pintype "passive"))
      (node (ref "U1") (pin "W29") (pinfunction "VDD_TOP_2_W29") (pintype "passive"))
      (node (ref "U1") (pin "W31") (pinfunction "VDD_TOP_2_W31") (pintype "passive"))
      (node (ref "U1") (pin "W33") (pinfunction "VDD_TOP_2_W33") (pintype "passive"))
      (node (ref "U1") (pin "W6") (pinfunction "VDD_TOP_1_W6") (pintype "passive"))
      (node (ref "U1") (pin "W8") (pinfunction "VDD_TOP_1_W8") (pintype "passive"))
      (node (ref "U1") (pin "Y11") (pinfunction "VDD_TOP_1_Y11") (pintype "passive"))
      (node (ref "U1") (pin "Y13") (pinfunction "VDD_TOP_1_Y13") (pintype "passive"))
      (node (ref "U1") (pin "Y15") (pinfunction "VDD_TOP_1_Y15") (pintype "passive"))
      (node (ref "U1") (pin "Y17") (pinfunction "VDD_TOP_1_Y17") (pintype "passive"))
      (node (ref "U1") (pin "Y20") (pinfunction "VDD_TOP_2_Y20") (pintype "passive"))
      (node (ref "U1") (pin "Y22") (pinfunction "VDD_TOP_2_Y22") (pintype "passive"))
      (node (ref "U1") (pin "Y24") (pinfunction "VDD_TOP_2_Y24") (pintype "passive"))
      (node (ref "U1") (pin "Y26") (pinfunction "VDD_TOP_2_Y26") (pintype "passive"))
      (node (ref "U1") (pin "Y28") (pinfunction "VDD_TOP_2_Y28") (pintype "passive"))
      (node (ref "U1") (pin "Y30") (pinfunction "VDD_TOP_2_Y30") (pintype "passive"))
      (node (ref "U1") (pin "Y32") (pinfunction "VDD_TOP_2_Y32") (pintype "passive"))
      (node (ref "U1") (pin "Y7") (pinfunction "VDD_TOP_1_Y7") (pintype "passive"))
      (node (ref "U1") (pin "Y9") (pinfunction "VDD_TOP_1_Y9") (pintype "passive"))
    )
    (net (code "2") (name "GND") (class "Default")
      (node (ref "C188") (pin "1") (pinfunction "1_1") (pintype "passive"))
      (node (ref "C189") (pin "1") (pinfunction "1_1") (pintype "passive"))
      (node (ref "C19") (pin "1") (pinfunction "1_1") (pintype "passive"))
      (node (ref "C190") (pin "1") (pinfunction "1_1") (pintype "passive"))
      (node (ref "C191") (pin "1") (pinfunction "1_1") (pintype "passive"))
      (node (ref "C192") (pin "1") (pinfunction "1_1") (pintype "passive"))
      (node (ref "C193") (pin "1") (pinfunction "1_1") (pintype "passive"))
      (node (ref "C194") (pin "1") (pinfunction "1_1") (pintype "passive"))
      (node (ref "C195") (pin "1") (pinfunction "1_1") (pintype "passive"))
      (node (ref "C196") (pin "1") (pinfunction "1_1") (pintype "passive"))
      (node (ref "C197") (pin "1") (pinfunction "1_1") (pintype "passive"))
      (node (ref "C198") (pin "1") (pinfunction "1_1") (pintype "passive"))
      (node (ref "C199") (pin "1") (pinfunction "1_1") (pintype "passive"))
      (node (ref "C200") (pin "1") (pinfunction "1_1") (pintype "passive"))
      (node (ref "C201") (pin "1") (pinfunction "1_1") (pintype "passive"))
      (node (ref "C202") (pin "1") (pinfunction "1_1") (pintype "passive"))
      (node (ref "C203") (pin "1") (pinfunction "1_1") (pintype "passive"))
      (node (ref "C204") (pin "1") (pinfunction "1_1") (pintype "passive"))
      (node (ref "C205") (pin "1") (pinfunction "1_1") (pintype "passive"))
      (node (ref "C206") (pin "1") (pinfunction "1_1") (pintype "passive"))
      (node (ref "C207") (pin "1") (pinfunction "1_1") (pintype "passive"))
      (node (ref "C208") (pin "1") (pinfunction "1_1") (pintype "passive"))
      (node (ref "C209") (pin "1") (pinfunction "1_1") (pintype "passive"))
      (node (ref "C210") (pin "1") (pinfunction "1_1") (pintype "passive"))
      (node (ref "C211") (pin "1") (pinfunction "1_1") (pintype "passive"))
      (node (ref "C212") (pin "1") (pinfunction "1_1") (pintype "passive"))
      (node (ref "C213") (pin "1") (pinfunction "1_1") (pintype "passive"))
      (node (ref "C214") (pin "1") (pinfunction "1_1") (pintype "passive"))
      (node (ref "C215") (pin "1") (pinfunction "1_1") (pintype "passive"))
      (node (ref "C216") (pin "1") (pinfunction "1_1") (pintype "passive"))
      (node (ref "C217") (pin "1") (pinfunction "1_1") (pintype "passive"))
      (node (ref "C218") (pin "1") (pinfunction "1_1") (pintype "passive"))
      (node (ref "C219") (pin "1") (pinfunction "1_1") (pintype "passive"))
      (node (ref "C220") (pin "1") (pinfunction "1_1") (pintype "passive"))
      (node (ref "C221") (pin "1") (pinfunction "1_1") (pintype "passive"))
      (node (ref "C222") (pin "1") (pinfunction "1_1") (pintype "passive"))
      (node (ref "C223") (pin "1") (pinfunction "1_1") (pintype "passive"))
      (node (ref "C224") (pin "1") (pinfunction "1_1") (pintype "passive"))
      (node (ref "C225") (pin "1") (pinfunction "1_1") (pintype "passive"))
      (node (ref "C226") (pin "1") (pinfunction "1_1") (pintype "passive"))
      (node (ref "C227") (pin "1") (pinfunction "1_1") (pintype "passive"))
      (node (ref "C228") (pin "1") (pinfunction "1_1") (pintype "passive"))
      (node (ref "C229") (pin "1") (pinfunction "1_1") (pintype "passive"))
      (node (ref "C230") (pin "1") (pinfunction "1_1") (pintype "passive"))
      (node (ref "C231") (pin "1") (pinfunction "1_1") (pintype "passive"))
      (node (ref "C232") (pin "1") (pinfunction "1_1") (pintype "passive"))
      (node (ref "C233") (pin "1") (pinfunction "1_1") (pintype "passive"))
      (node (ref "C234") (pin "1") (pinfunction "1_1") (pintype "passive"))
      (node (ref "C235") (pin "1") (pinfunction "1_1") (pintype "passive"))
      (node (ref "C237") (pin "1") (pinfunction "1_1") (pintype "passive"))
      (node (ref "C238") (pin "1") (pinfunction "1_1") (pintype "passive"))
      (node (ref "C239") (pin "1") (pinfunction "1_1") (pintype "passive"))
      (node (ref "C240") (pin "1") (pinfunction "1_1") (pintype "passive"))
      (node (ref "C241") (pin "1") (pinfunction "1_1") (pintype "passive"))
      (node (ref "C242") (pin "1") (pinfunction "1_1") (pintype "passive"))
      (node (ref "C243") (pin "1") (pinfunction "1_1") (pintype "passive"))
      (node (ref "C244") (pin "1") (pinfunction "1_1") (pintype "passive"))
      (node (ref "C245") (pin "1") (pinfunction "1_1") (pintype "passive"))
      (node (ref "C246") (pin "1") (pinfunction "1_1") (pintype "passive"))
      (node (ref "C247") (pin "1") (pinfunction "1_1") (pintype "passive"))
      (node (ref "C248") (pin "1") (pinfunction "1_1") (pintype "passive"))
      (node (ref "C249") (pin "1") (pinfunction "1_1") (pintype "passive"))
      (node (ref "C250") (pin "1") (pinfunction "1_1") (pintype "passive"))
      (node (ref "C251") (pin "1") (pinfunction "1_1") (pintype "passive"))
      (node (ref "C252") (pin "1") (pinfunction "1_1") (pintype "passive"))
      (node (ref "C253") (pin "1") (pinfunction "1_1") (pintype "passive"))
      (node (ref "C254") (pin "1") (pinfunction "1_1") (pintype "passive"))
      (node (ref "C255") (pin "1") (pinfunction "1_1") (pintype "passive"))
      (node (ref "C256") (pin "1") (pinfunction "1_1") (pintype "passive"))
      (node (ref "C257") (pin "1") (pinfunction "1_1") (pintype "passive"))
      (node (ref "C258") (pin "1") (pinfunction "1_1") (pintype "passive"))
      (node (ref "C259") (pin "1") (pinfunction "1_1") (pintype "passive"))
      (node (ref "C260") (pin "1") (pinfunction "1_1") (pintype "passive"))
      (node (ref "C261") (pin "1") (pinfunction "1_1") (pintype "passive"))
      (node (ref "C262") (pin "1") (pinfunction "1_1") (pintype "passive"))
      (node (ref "C263") (pin "1") (pinfunction "1_1") (pintype "passive"))
      (node (ref "C264") (pin "1") (pinfunction "1_1") (pintype "passive"))
      (node (ref "C265") (pin "1") (pinfunction "1_1") (pintype "passive"))
      (node (ref "C266") (pin "1") (pinfunction "1_1") (pintype "passive"))
      (node (ref "C36") (pin "1") (pinfunction "1_1") (pintype "passive"))
      (node (ref "U1") (pin "A1") (pinfunction "VSS_A1") (pintype "passive"))
      (node (ref "U1") (pin "A10") (pinfunction "VSS_A10") (pintype "passive"))
      (node (ref "U1") (pin "A12") (pinfunction "VSS_A12") (pintype "passive"))
      (node (ref "U1") (pin "A19") (pinfunction "VSS_A19") (pintype "passive"))
      (node (ref "U1") (pin "A2") (pinfunction "VSS_A2") (pintype "passive"))
      (node (ref "U1") (pin "A29") (pinfunction "VSS_A29") (pintype "passive"))
      (node (ref "U1") (pin "A35") (pinfunction "VSS_A35") (pintype "passive"))
      (node (ref "U1") (pin "A36") (pinfunction "VSS_A36") (pintype "passive"))
      (node (ref "U1") (pin "AA11") (pinfunction "VSS_AA11") (pintype "passive"))
      (node (ref "U1") (pin "AA13") (pinfunction "VSS_AA13") (pintype "passive"))
      (node (ref "U1") (pin "AA15") (pinfunction "VSS_AA15") (pintype "passive"))
      (node (ref "U1") (pin "AA17") (pinfunction "VSS_AA17") (pintype "passive"))
      (node (ref "U1") (pin "AA20") (pinfunction "VSS_AA20") (pintype "passive"))
      (node (ref "U1") (pin "AA22") (pinfunction "VSS_AA22") (pintype "passive"))
      (node (ref "U1") (pin "AA24") (pinfunction "VSS_AA24") (pintype "passive"))
      (node (ref "U1") (pin "AA26") (pinfunction "VSS_AA26") (pintype "passive"))
      (node (ref "U1") (pin "AA28") (pinfunction "VSS_AA28") (pintype "passive"))
      (node (ref "U1") (pin "AA3") (pinfunction "VSS_AA3") (pintype "passive"))
      (node (ref "U1") (pin "AA30") (pinfunction "VSS_AA30") (pintype "passive"))
      (node (ref "U1") (pin "AA32") (pinfunction "VSS_AA32") (pintype "passive"))
      (node (ref "U1") (pin "AA5") (pinfunction "VSS_AA5") (pintype "passive"))
      (node (ref "U1") (pin "AA7") (pinfunction "VSS_AA7") (pintype "passive"))
      (node (ref "U1") (pin "AA9") (pinfunction "VSS_AA9") (pintype "passive"))
      (node (ref "U1") (pin "AB10") (pinfunction "VSS_AB10") (pintype "passive"))
      (node (ref "U1") (pin "AB12") (pinfunction "VSS_AB12") (pintype "passive"))
      (node (ref "U1") (pin "AB14") (pinfunction "VSS_AB14") (pintype "passive"))
      (node (ref "U1") (pin "AB16") (pinfunction "VSS_AB16") (pintype "passive"))
      (node (ref "U1") (pin "AB18") (pinfunction "VSS_AB18") (pintype "passive"))
      (node (ref "U1") (pin "AB19") (pinfunction "VSS_AB19") (pintype "passive"))
      (node (ref "U1") (pin "AB21") (pinfunction "VSS_AB21") (pintype "passive"))
      (node (ref "U1") (pin "AB23") (pinfunction "VSS_AB23") (pintype "passive"))
      (node (ref "U1") (pin "AB25") (pinfunction "VSS_AB25") (pintype "passive"))
      (node (ref "U1") (pin "AB27") (pinfunction "VSS_AB27") (pintype "passive"))
      (node (ref "U1") (pin "AB29") (pinfunction "VSS_AB29") (pintype "passive"))
      (node (ref "U1") (pin "AB31") (pinfunction "VSS_AB31") (pintype "passive"))
      (node (ref "U1") (pin "AB6") (pinfunction "VSS_AB6") (pintype "passive"))
      (node (ref "U1") (pin "AB8") (pinfunction "VSS_AB8") (pintype "passive"))
      (node (ref "U1") (pin "AC11") (pinfunction "VSS_AC11") (pintype "passive"))
      (node (ref "U1") (pin "AC13") (pinfunction "VSS_AC13") (pintype "passive"))
      (node (ref "U1") (pin "AC15") (pinfunction "VSS_AC15") (pintype "passive"))
      (node (ref "U1") (pin "AC17") (pinfunction "VSS_AC17") (pintype "passive"))
      (node (ref "U1") (pin "AC20") (pinfunction "VSS_AC20") (pintype "passive"))
      (node (ref "U1") (pin "AC22") (pinfunction "VSS_AC22") (pintype "passive"))
      (node (ref "U1") (pin "AC24") (pinfunction "VSS_AC24") (pintype "passive"))
      (node (ref "U1") (pin "AC26") (pinfunction "VSS_AC26") (pintype "passive"))
      (node (ref "U1") (pin "AC28") (pinfunction "VSS_AC28") (pintype "passive"))
      (node (ref "U1") (pin "AC30") (pinfunction "VSS_AC30") (pintype "passive"))
      (node (ref "U1") (pin "AC32") (pinfunction "VSS_AC32") (pintype "passive"))
      (node (ref "U1") (pin "AC34") (pinfunction "VSS_AC34") (pintype "passive"))
      (node (ref "U1") (pin "AC5") (pinfunction "VSS_AC5") (pintype "passive"))
      (node (ref "U1") (pin "AC7") (pinfunction "VSS_AC7") (pintype "passive"))
      (node (ref "U1") (pin "AC9") (pinfunction "VSS_AC9") (pintype "passive"))
      (node (ref "U1") (pin "AD10") (pinfunction "VSS_AD10") (pintype "passive"))
      (node (ref "U1") (pin "AD12") (pinfunction "VSS_AD12") (pintype "passive"))
      (node (ref "U1") (pin "AD14") (pinfunction "VSS_AD14") (pintype "passive"))
      (node (ref "U1") (pin "AD16") (pinfunction "VSS_AD16") (pintype "passive"))
      (node (ref "U1") (pin "AD18") (pinfunction "VSS_AD18") (pintype "passive"))
      (node (ref "U1") (pin "AD19") (pinfunction "VSS_AD19") (pintype "passive"))
      (node (ref "U1") (pin "AD21") (pinfunction "VSS_AD21") (pintype "passive"))
      (node (ref "U1") (pin "AD23") (pinfunction "VSS_AD23") (pintype "passive"))
      (node (ref "U1") (pin "AD25") (pinfunction "VSS_AD25") (pintype "passive"))
      (node (ref "U1") (pin "AD27") (pinfunction "VSS_AD27") (pintype "passive"))
      (node (ref "U1") (pin "AD29") (pinfunction "VSS_AD29") (pintype "passive"))
      (node (ref "U1") (pin "AD31") (pinfunction "VSS_AD31") (pintype "passive"))
      (node (ref "U1") (pin "AD4") (pinfunction "VSS_AD4") (pintype "passive"))
      (node (ref "U1") (pin "AD6") (pinfunction "VSS_AD6") (pintype "passive"))
      (node (ref "U1") (pin "AD8") (pinfunction "VSS_AD8") (pintype "passive"))
      (node (ref "U1") (pin "AE1") (pinfunction "VSS_AE1") (pintype "passive"))
      (node (ref "U1") (pin "AE11") (pinfunction "VSS_AE11") (pintype "passive"))
      (node (ref "U1") (pin "AE13") (pinfunction "VSS_AE13") (pintype "passive"))
      (node (ref "U1") (pin "AE15") (pinfunction "VSS_AE15") (pintype "passive"))
      (node (ref "U1") (pin "AE17") (pinfunction "VSS_AE17") (pintype "passive"))
      (node (ref "U1") (pin "AE20") (pinfunction "VSS_AE20") (pintype "passive"))
      (node (ref "U1") (pin "AE22") (pinfunction "VSS_AE22") (pintype "passive"))
      (node (ref "U1") (pin "AE24") (pinfunction "VSS_AE24") (pintype "passive"))
      (node (ref "U1") (pin "AE26") (pinfunction "VSS_AE26") (pintype "passive"))
      (node (ref "U1") (pin "AE28") (pinfunction "VSS_AE28") (pintype "passive"))
      (node (ref "U1") (pin "AE30") (pinfunction "VSS_AE30") (pintype "passive"))
      (node (ref "U1") (pin "AE32") (pinfunction "VSS_AE32") (pintype "passive"))
      (node (ref "U1") (pin "AE5") (pinfunction "VSS_AE5") (pintype "passive"))
      (node (ref "U1") (pin "AE7") (pinfunction "VSS_AE7") (pintype "passive"))
      (node (ref "U1") (pin "AE9") (pinfunction "VSS_AE9") (pintype "passive"))
      (node (ref "U1") (pin "AF10") (pinfunction "VSS_AF10") (pintype "passive"))
      (node (ref "U1") (pin "AF12") (pinfunction "VSS_AF12") (pintype "passive"))
      (node (ref "U1") (pin "AF14") (pinfunction "VSS_AF14") (pintype "passive"))
      (node (ref "U1") (pin "AF16") (pinfunction "VSS_AF16") (pintype "passive"))
      (node (ref "U1") (pin "AF18") (pinfunction "VSS_AF18") (pintype "passive"))
      (node (ref "U1") (pin "AF19") (pinfunction "VSS_AF19") (pintype "passive"))
      (node (ref "U1") (pin "AF21") (pinfunction "VSS_AF21") (pintype "passive"))
      (node (ref "U1") (pin "AF23") (pinfunction "VSS_AF23") (pintype "passive"))
      (node (ref "U1") (pin "AF25") (pinfunction "VSS_AF25") (pintype "passive"))
      (node (ref "U1") (pin "AF27") (pinfunction "VSS_AF27") (pintype "passive"))
      (node (ref "U1") (pin "AF29") (pinfunction "VSS_AF29") (pintype "passive"))
      (node (ref "U1") (pin "AF31") (pinfunction "VSS_AF31") (pintype "passive"))
      (node (ref "U1") (pin "AF35") (pinfunction "VSS_AF35") (pintype "passive"))
      (node (ref "U1") (pin "AF8") (pinfunction "VSS_AF8") (pintype "passive"))
      (node (ref "U1") (pin "AG1") (pinfunction "VSS_AG1") (pintype "passive"))
      (node (ref "U1") (pin "AG11") (pinfunction "VSS_AG11") (pintype "passive"))
      (node (ref "U1") (pin "AG13") (pinfunction "VSS_AG13") (pintype "passive"))
      (node (ref "U1") (pin "AG15") (pinfunction "VSS_AG15") (pintype "passive"))
      (node (ref "U1") (pin "AG17") (pinfunction "VSS_AG17") (pintype "passive"))
      (node (ref "U1") (pin "AG20") (pinfunction "VSS_AG20") (pintype "passive"))
      (node (ref "U1") (pin "AG22") (pinfunction "VSS_AG22") (pintype "passive"))
      (node (ref "U1") (pin "AG24") (pinfunction "VSS_AG24") (pintype "passive"))
      (node (ref "U1") (pin "AG26") (pinfunction "VSS_AG26") (pintype "passive"))
      (node (ref "U1") (pin "AG28") (pinfunction "VSS_AG28") (pintype "passive"))
      (node (ref "U1") (pin "AG30") (pinfunction "VSS_AG30") (pintype "passive"))
      (node (ref "U1") (pin "AG32") (pinfunction "VSS_AG32") (pintype "passive"))
      (node (ref "U1") (pin "AG5") (pinfunction "VSS_AG5") (pintype "passive"))
      (node (ref "U1") (pin "AG7") (pinfunction "VSS_AG7") (pintype "passive"))
      (node (ref "U1") (pin "AG9") (pinfunction "VSS_AG9") (pintype "passive"))
      (node (ref "U1") (pin "AH10") (pinfunction "VSS_AH10") (pintype "passive"))
      (node (ref "U1") (pin "AH12") (pinfunction "VSS_AH12") (pintype "passive"))
      (node (ref "U1") (pin "AH14") (pinfunction "VSS_AH14") (pintype "passive"))
      (node (ref "U1") (pin "AH16") (pinfunction "VSS_AH16") (pintype "passive"))
      (node (ref "U1") (pin "AH18") (pinfunction "VSS_AH18") (pintype "passive"))
      (node (ref "U1") (pin "AH19") (pinfunction "VSS_AH19") (pintype "passive"))
      (node (ref "U1") (pin "AH2") (pinfunction "VSS_AH2") (pintype "passive"))
      (node (ref "U1") (pin "AH21") (pinfunction "VSS_AH21") (pintype "passive"))
      (node (ref "U1") (pin "AH23") (pinfunction "VSS_AH23") (pintype "passive"))
      (node (ref "U1") (pin "AH25") (pinfunction "VSS_AH25") (pintype "passive"))
      (node (ref "U1") (pin "AH27") (pinfunction "VSS_AH27") (pintype "passive"))
      (node (ref "U1") (pin "AH29") (pinfunction "VSS_AH29") (pintype "passive"))
      (node (ref "U1") (pin "AH31") (pinfunction "VSS_AH31") (pintype "passive"))
      (node (ref "U1") (pin "AH6") (pinfunction "VSS_AH6") (pintype "passive"))
      (node (ref "U1") (pin "AH8") (pinfunction "VSS_AH8") (pintype "passive"))
      (node (ref "U1") (pin "AJ11") (pinfunction "VSS_AJ11") (pintype "passive"))
      (node (ref "U1") (pin "AJ13") (pinfunction "VSS_AJ13") (pintype "passive"))
      (node (ref "U1") (pin "AJ15") (pinfunction "VSS_AJ15") (pintype "passive"))
      (node (ref "U1") (pin "AJ17") (pinfunction "VSS_AJ17") (pintype "passive"))
      (node (ref "U1") (pin "AJ20") (pinfunction "VSS_AJ20") (pintype "passive"))
      (node (ref "U1") (pin "AJ22") (pinfunction "VSS_AJ22") (pintype "passive"))
      (node (ref "U1") (pin "AJ24") (pinfunction "VSS_AJ24") (pintype "passive"))
      (node (ref "U1") (pin "AJ26") (pinfunction "VSS_AJ26") (pintype "passive"))
      (node (ref "U1") (pin "AJ28") (pinfunction "VSS_AJ28") (pintype "passive"))
      (node (ref "U1") (pin "AJ30") (pinfunction "VSS_AJ30") (pintype "passive"))
      (node (ref "U1") (pin "AJ32") (pinfunction "VSS_AJ32") (pintype "passive"))
      (node (ref "U1") (pin "AJ36") (pinfunction "VSS_AJ36") (pintype "passive"))
      (node (ref "U1") (pin "AJ5") (pinfunction "VSS_AJ5") (pintype "passive"))
      (node (ref "U1") (pin "AJ7") (pinfunction "VSS_AJ7") (pintype "passive"))
      (node (ref "U1") (pin "AJ9") (pinfunction "VSS_AJ9") (pintype "passive"))
      (node (ref "U1") (pin "AK10") (pinfunction "VSS_AK10") (pintype "passive"))
      (node (ref "U1") (pin "AK12") (pinfunction "VSS_AK12") (pintype "passive"))
      (node (ref "U1") (pin "AK14") (pinfunction "VSS_AK14") (pintype "passive"))
      (node (ref "U1") (pin "AK16") (pinfunction "VSS_AK16") (pintype "passive"))
      (node (ref "U1") (pin "AK18") (pinfunction "VSS_AK18") (pintype "passive"))
      (node (ref "U1") (pin "AK19") (pinfunction "VSS_AK19") (pintype "passive"))
      (node (ref "U1") (pin "AK21") (pinfunction "VSS_AK21") (pintype "passive"))
      (node (ref "U1") (pin "AK23") (pinfunction "VSS_AK23") (pintype "passive"))
      (node (ref "U1") (pin "AK25") (pinfunction "VSS_AK25") (pintype "passive"))
      (node (ref "U1") (pin "AK27") (pinfunction "VSS_AK27") (pintype "passive"))
      (node (ref "U1") (pin "AK29") (pinfunction "VSS_AK29") (pintype "passive"))
      (node (ref "U1") (pin "AK31") (pinfunction "VSS_AK31") (pintype "passive"))
      (node (ref "U1") (pin "AK33") (pinfunction "VSS_AK33") (pintype "passive"))
      (node (ref "U1") (pin "AK6") (pinfunction "VSS_AK6") (pintype "passive"))
      (node (ref "U1") (pin "AK8") (pinfunction "VSS_AK8") (pintype "passive"))
      (node (ref "U1") (pin "AL11") (pinfunction "VSS_AL11") (pintype "passive"))
      (node (ref "U1") (pin "AL13") (pinfunction "VSS_AL13") (pintype "passive"))
      (node (ref "U1") (pin "AL15") (pinfunction "VSS_AL15") (pintype "passive"))
      (node (ref "U1") (pin "AL17") (pinfunction "VSS_AL17") (pintype "passive"))
      (node (ref "U1") (pin "AL20") (pinfunction "VSS_AL20") (pintype "passive"))
      (node (ref "U1") (pin "AL22") (pinfunction "VSS_AL22") (pintype "passive"))
      (node (ref "U1") (pin "AL24") (pinfunction "VSS_AL24") (pintype "passive"))
      (node (ref "U1") (pin "AL28") (pinfunction "VSS_AL28") (pintype "passive"))
      (node (ref "U1") (pin "AL3") (pinfunction "VSS_AL3") (pintype "passive"))
      (node (ref "U1") (pin "AL30") (pinfunction "VSS_AL30") (pintype "passive"))
      (node (ref "U1") (pin "AL5") (pinfunction "VSS_AL5") (pintype "passive"))
      (node (ref "U1") (pin "AL7") (pinfunction "VSS_AL7") (pintype "passive"))
      (node (ref "U1") (pin "AL9") (pinfunction "VSS_AL9") (pintype "passive"))
      (node (ref "U1") (pin "AM10") (pinfunction "VSS_AM10") (pintype "passive"))
      (node (ref "U1") (pin "AM12") (pinfunction "VSS_AM12") (pintype "passive"))
      (node (ref "U1") (pin "AM14") (pinfunction "VSS_AM14") (pintype "passive"))
      (node (ref "U1") (pin "AM16") (pinfunction "VSS_AM16") (pintype "passive"))
      (node (ref "U1") (pin "AM18") (pinfunction "VSS_AM18") (pintype "passive"))
      (node (ref "U1") (pin "AM20") (pinfunction "VSS_AM20") (pintype "passive"))
      (node (ref "U1") (pin "AM21") (pinfunction "VSS_AM21") (pintype "passive"))
      (node (ref "U1") (pin "AM23") (pinfunction "VSS_AM23") (pintype "passive"))
      (node (ref "U1") (pin "AM25") (pinfunction "VSS_AM25") (pintype "passive"))
      (node (ref "U1") (pin "AM27") (pinfunction "VSS_AM27") (pintype "passive"))
      (node (ref "U1") (pin "AM29") (pinfunction "VSS_AM29") (pintype "passive"))
      (node (ref "U1") (pin "AM31") (pinfunction "VSS_AM31") (pintype "passive"))
      (node (ref "U1") (pin "AM35") (pinfunction "VSS_AM35") (pintype "passive"))
      (node (ref "U1") (pin "AM8") (pinfunction "VSS_AM8") (pintype "passive"))
      (node (ref "U1") (pin "AN17") (pinfunction "VSS_AN17") (pintype "passive"))
      (node (ref "U1") (pin "AN24") (pinfunction "VSS_AN24") (pintype "passive"))
      (node (ref "U1") (pin "AN34") (pinfunction "VSS_AN34") (pintype "passive"))
      (node (ref "U1") (pin "AN7") (pinfunction "VSS_AN7") (pintype "passive"))
      (node (ref "U1") (pin "AP14") (pinfunction "VSS_AP14") (pintype "passive"))
      (node (ref "U1") (pin "AP18") (pinfunction "VSS_AP18") (pintype "passive"))
      (node (ref "U1") (pin "AP21") (pinfunction "VSS_AP21") (pintype "passive"))
      (node (ref "U1") (pin "AP31") (pinfunction "VSS_AP31") (pintype "passive"))
      (node (ref "U1") (pin "AP4") (pinfunction "VSS_AP4") (pintype "passive"))
      (node (ref "U1") (pin "AR1") (pinfunction "VSS_AR1") (pintype "passive"))
      (node (ref "U1") (pin "AR11") (pinfunction "VSS_AR11") (pintype "passive"))
      (node (ref "U1") (pin "AR28") (pinfunction "VSS_AR28") (pintype "passive"))
      (node (ref "U1") (pin "AR36") (pinfunction "VSS_AR36") (pintype "passive"))
      (node (ref "U1") (pin "AR5") (pinfunction "VSS_AR5") (pintype "passive"))
      (node (ref "U1") (pin "AT1") (pinfunction "VSS_AT1") (pintype "passive"))
      (node (ref "U1") (pin "AT18") (pinfunction "VSS_AT18") (pintype "passive"))
      (node (ref "U1") (pin "AT2") (pinfunction "VSS_AT2") (pintype "passive"))
      (node (ref "U1") (pin "AT25") (pinfunction "VSS_AT25") (pintype "passive"))
      (node (ref "U1") (pin "AT27") (pinfunction "VSS_AT27") (pintype "passive"))
      (node (ref "U1") (pin "AT35") (pinfunction "VSS_AT35") (pintype "passive"))
      (node (ref "U1") (pin "AT36") (pinfunction "VSS_AT36") (pintype "passive"))
      (node (ref "U1") (pin "AT8") (pinfunction "VSS_AT8") (pintype "passive"))
      (node (ref "U1") (pin "B1") (pinfunction "VSS_B1") (pintype "passive"))
      (node (ref "U1") (pin "B26") (pinfunction "VSS_B26") (pintype "passive"))
      (node (ref "U1") (pin "B32") (pinfunction "VSS_B32") (pintype "passive"))
      (node (ref "U1") (pin "B36") (pinfunction "VSS_B36") (pintype "passive"))
      (node (ref "U1") (pin "B9") (pinfunction "VSS_B9") (pintype "passive"))
      (node (ref "U1") (pin "C16") (pinfunction "VSS_C16") (pintype "passive"))
      (node (ref "U1") (pin "C19") (pinfunction "VSS_C19") (pintype "passive"))
      (node (ref "U1") (pin "C23") (pinfunction "VSS_C23") (pintype "passive"))
      (node (ref "U1") (pin "C33") (pinfunction "VSS_C33") (pintype "passive"))
      (node (ref "U1") (pin "C6") (pinfunction "VSS_C6") (pintype "passive"))
      (node (ref "U1") (pin "D13") (pinfunction "VSS_D13") (pintype "passive"))
      (node (ref "U1") (pin "D20") (pinfunction "VSS_D20") (pintype "passive"))
      (node (ref "U1") (pin "D3") (pinfunction "VSS_D3") (pintype "passive"))
      (node (ref "U1") (pin "D30") (pinfunction "VSS_D30") (pintype "passive"))
      (node (ref "U1") (pin "E10") (pinfunction "VSS_E10") (pintype "passive"))
      (node (ref "U1") (pin "E12") (pinfunction "VSS_E12") (pintype "passive"))
      (node (ref "U1") (pin "E14") (pinfunction "VSS_E14") (pintype "passive"))
      (node (ref "U1") (pin "E16") (pinfunction "VSS_E16") (pintype "passive"))
      (node (ref "U1") (pin "E17") (pinfunction "VSS_E17") (pintype "passive"))
      (node (ref "U1") (pin "E19") (pinfunction "VSS_E19") (pintype "passive"))
      (node (ref "U1") (pin "E2") (pinfunction "VSS_E2") (pintype "passive"))
      (node (ref "U1") (pin "E21") (pinfunction "VSS_E21") (pintype "passive"))
      (node (ref "U1") (pin "E23") (pinfunction "VSS_E23") (pintype "passive"))
      (node (ref "U1") (pin "E25") (pinfunction "VSS_E25") (pintype "passive"))
      (node (ref "U1") (pin "E27") (pinfunction "VSS_E27") (pintype "passive"))
      (node (ref "U1") (pin "E29") (pinfunction "VSS_E29") (pintype "passive"))
      (node (ref "U1") (pin "E6") (pinfunction "VSS_E6") (pintype "passive"))
      (node (ref "U1") (pin "E8") (pinfunction "VSS_E8") (pintype "passive"))
      (node (ref "U1") (pin "F13") (pinfunction "VSS_F13") (pintype "passive"))
      (node (ref "U1") (pin "F15") (pinfunction "VSS_F15") (pintype "passive"))
      (node (ref "U1") (pin "F17") (pinfunction "VSS_F17") (pintype "passive"))
      (node (ref "U1") (pin "F20") (pinfunction "VSS_F20") (pintype "passive"))
      (node (ref "U1") (pin "F22") (pinfunction "VSS_F22") (pintype "passive"))
      (node (ref "U1") (pin "F24") (pinfunction "VSS_F24") (pintype "passive"))
      (node (ref "U1") (pin "F26") (pinfunction "VSS_F26") (pintype "passive"))
      (node (ref "U1") (pin "F28") (pinfunction "VSS_F28") (pintype "passive"))
      (node (ref "U1") (pin "F30") (pinfunction "VSS_F30") (pintype "passive"))
      (node (ref "U1") (pin "F32") (pinfunction "VSS_F32") (pintype "passive"))
      (node (ref "U1") (pin "F34") (pinfunction "VSS_F34") (pintype "passive"))
      (node (ref "U1") (pin "F7") (pinfunction "VSS_F7") (pintype "passive"))
      (node (ref "U1") (pin "F9") (pinfunction "VSS_F9") (pintype "passive"))
      (node (ref "U1") (pin "G10") (pinfunction "VSS_G10") (pintype "passive"))
      (node (ref "U1") (pin "G12") (pinfunction "VSS_G12") (pintype "passive"))
      (node (ref "U1") (pin "G14") (pinfunction "VSS_G14") (pintype "passive"))
      (node (ref "U1") (pin "G16") (pinfunction "VSS_G16") (pintype "passive"))
      (node (ref "U1") (pin "G18") (pinfunction "VSS_G18") (pintype "passive"))
      (node (ref "U1") (pin "G19") (pinfunction "VSS_G19") (pintype "passive"))
      (node (ref "U1") (pin "G21") (pinfunction "VSS_G21") (pintype "passive"))
      (node (ref "U1") (pin "G23") (pinfunction "VSS_G23") (pintype "passive"))
      (node (ref "U1") (pin "G25") (pinfunction "VSS_G25") (pintype "passive"))
      (node (ref "U1") (pin "G27") (pinfunction "VSS_G27") (pintype "passive"))
      (node (ref "U1") (pin "G29") (pinfunction "VSS_G29") (pintype "passive"))
      (node (ref "U1") (pin "G31") (pinfunction "VSS_G31") (pintype "passive"))
      (node (ref "U1") (pin "G4") (pinfunction "VSS_G4") (pintype "passive"))
      (node (ref "U1") (pin "G6") (pinfunction "VSS_G6") (pintype "passive"))
      (node (ref "U1") (pin "G8") (pinfunction "VSS_G8") (pintype "passive"))
      (node (ref "U1") (pin "H1") (pinfunction "VSS_H1") (pintype "passive"))
      (node (ref "U1") (pin "H11") (pinfunction "VSS_H11") (pintype "passive"))
      (node (ref "U1") (pin "H13") (pinfunction "VSS_H13") (pintype "passive"))
      (node (ref "U1") (pin "H15") (pinfunction "VSS_H15") (pintype "passive"))
      (node (ref "U1") (pin "H17") (pinfunction "VSS_H17") (pintype "passive"))
      (node (ref "U1") (pin "H20") (pinfunction "VSS_H20") (pintype "passive"))
      (node (ref "U1") (pin "H22") (pinfunction "VSS_H22") (pintype "passive"))
      (node (ref "U1") (pin "H24") (pinfunction "VSS_H24") (pintype "passive"))
      (node (ref "U1") (pin "H26") (pinfunction "VSS_H26") (pintype "passive"))
      (node (ref "U1") (pin "H28") (pinfunction "VSS_H28") (pintype "passive"))
      (node (ref "U1") (pin "H30") (pinfunction "VSS_H30") (pintype "passive"))
      (node (ref "U1") (pin "H32") (pinfunction "VSS_H32") (pintype "passive"))
      (node (ref "U1") (pin "H5") (pinfunction "VSS_H5") (pintype "passive"))
      (node (ref "U1") (pin "H7") (pinfunction "VSS_H7") (pintype "passive"))
      (node (ref "U1") (pin "H9") (pinfunction "VSS_H9") (pintype "passive"))
      (node (ref "U1") (pin "J10") (pinfunction "VSS_J10") (pintype "passive"))
      (node (ref "U1") (pin "J12") (pinfunction "VSS_J12") (pintype "passive"))
      (node (ref "U1") (pin "J14") (pinfunction "VSS_J14") (pintype "passive"))
      (node (ref "U1") (pin "J16") (pinfunction "VSS_J16") (pintype "passive"))
      (node (ref "U1") (pin "J18") (pinfunction "VSS_J18") (pintype "passive"))
      (node (ref "U1") (pin "J19") (pinfunction "VSS_J19") (pintype "passive"))
      (node (ref "U1") (pin "J21") (pinfunction "VSS_J21") (pintype "passive"))
      (node (ref "U1") (pin "J23") (pinfunction "VSS_J23") (pintype "passive"))
      (node (ref "U1") (pin "J25") (pinfunction "VSS_J25") (pintype "passive"))
      (node (ref "U1") (pin "J27") (pinfunction "VSS_J27") (pintype "passive"))
      (node (ref "U1") (pin "J29") (pinfunction "VSS_J29") (pintype "passive"))
      (node (ref "U1") (pin "J31") (pinfunction "VSS_J31") (pintype "passive"))
      (node (ref "U1") (pin "J35") (pinfunction "VSS_J35") (pintype "passive"))
      (node (ref "U1") (pin "J6") (pinfunction "VSS_J6") (pintype "passive"))
      (node (ref "U1") (pin "J8") (pinfunction "VSS_J8") (pintype "passive"))
      (node (ref "U1") (pin "K11") (pinfunction "VSS_K11") (pintype "passive"))
      (node (ref "U1") (pin "K13") (pinfunction "VSS_K13") (pintype "passive"))
      (node (ref "U1") (pin "K15") (pinfunction "VSS_K15") (pintype "passive"))
      (node (ref "U1") (pin "K17") (pinfunction "VSS_K17") (pintype "passive"))
      (node (ref "U1") (pin "K20") (pinfunction "VSS_K20") (pintype "passive"))
      (node (ref "U1") (pin "K22") (pinfunction "VSS_K22") (pintype "passive"))
      (node (ref "U1") (pin "K24") (pinfunction "VSS_K24") (pintype "passive"))
      (node (ref "U1") (pin "K26") (pinfunction "VSS_K26") (pintype "passive"))
      (node (ref "U1") (pin "K28") (pinfunction "VSS_K28") (pintype "passive"))
      (node (ref "U1") (pin "K30") (pinfunction "VSS_K30") (pintype "passive"))
      (node (ref "U1") (pin "K32") (pinfunction "VSS_K32") (pintype "passive"))
      (node (ref "U1") (pin "K36") (pinfunction "VSS_K36") (pintype "passive"))
      (node (ref "U1") (pin "K5") (pinfunction "VSS_K5") (pintype "passive"))
      (node (ref "U1") (pin "K7") (pinfunction "VSS_K7") (pintype "passive"))
      (node (ref "U1") (pin "K9") (pinfunction "VSS_K9") (pintype "passive"))
      (node (ref "U1") (pin "L10") (pinfunction "VSS_L10") (pintype "passive"))
      (node (ref "U1") (pin "L12") (pinfunction "VSS_L12") (pintype "passive"))
      (node (ref "U1") (pin "L14") (pinfunction "VSS_L14") (pintype "passive"))
      (node (ref "U1") (pin "L16") (pinfunction "VSS_L16") (pintype "passive"))
      (node (ref "U1") (pin "L18") (pinfunction "VSS_L18") (pintype "passive"))
      (node (ref "U1") (pin "L19") (pinfunction "VSS_L19") (pintype "passive"))
      (node (ref "U1") (pin "L2") (pinfunction "VSS_L2") (pintype "passive"))
      (node (ref "U1") (pin "L21") (pinfunction "VSS_L21") (pintype "passive"))
      (node (ref "U1") (pin "L23") (pinfunction "VSS_L23") (pintype "passive"))
      (node (ref "U1") (pin "L25") (pinfunction "VSS_L25") (pintype "passive"))
      (node (ref "U1") (pin "L27") (pinfunction "VSS_L27") (pintype "passive"))
      (node (ref "U1") (pin "L29") (pinfunction "VSS_L29") (pintype "passive"))
      (node (ref "U1") (pin "L6") (pinfunction "VSS_L6") (pintype "passive"))
      (node (ref "U1") (pin "L8") (pinfunction "VSS_L8") (pintype "passive"))
      (node (ref "U1") (pin "M11") (pinfunction "VSS_M11") (pintype "passive"))
      (node (ref "U1") (pin "M13") (pinfunction "VSS_M13") (pintype "passive"))
      (node (ref "U1") (pin "M15") (pinfunction "VSS_M15") (pintype "passive"))
      (node (ref "U1") (pin "M17") (pinfunction "VSS_M17") (pintype "passive"))
      (node (ref "U1") (pin "M20") (pinfunction "VSS_M20") (pintype "passive"))
      (node (ref "U1") (pin "M22") (pinfunction "VSS_M22") (pintype "passive"))
      (node (ref "U1") (pin "M24") (pinfunction "VSS_M24") (pintype "passive"))
      (node (ref "U1") (pin "M26") (pinfunction "VSS_M26") (pintype "passive"))
      (node (ref "U1") (pin "M28") (pinfunction "VSS_M28") (pintype "passive"))
      (node (ref "U1") (pin "M30") (pinfunction "VSS_M30") (pintype "passive"))
      (node (ref "U1") (pin "M32") (pinfunction "VSS_M32") (pintype "passive"))
      (node (ref "U1") (pin "M36") (pinfunction "VSS_M36") (pintype "passive"))
      (node (ref "U1") (pin "M5") (pinfunction "VSS_M5") (pintype "passive"))
      (node (ref "U1") (pin "M7") (pinfunction "VSS_M7") (pintype "passive"))
      (node (ref "U1") (pin "M9") (pinfunction "VSS_M9") (pintype "passive"))
      (node (ref "U1") (pin "N10") (pinfunction "VSS_N10") (pintype "passive"))
      (node (ref "U1") (pin "N12") (pinfunction "VSS_N12") (pintype "passive"))
      (node (ref "U1") (pin "N14") (pinfunction "VSS_N14") (pintype "passive"))
      (node (ref "U1") (pin "N16") (pinfunction "VSS_N16") (pintype "passive"))
      (node (ref "U1") (pin "N18") (pinfunction "VSS_N18") (pintype "passive"))
      (node (ref "U1") (pin "N19") (pinfunction "VSS_N19") (pintype "passive"))
      (node (ref "U1") (pin "N21") (pinfunction "VSS_N21") (pintype "passive"))
      (node (ref "U1") (pin "N23") (pinfunction "VSS_N23") (pintype "passive"))
      (node (ref "U1") (pin "N25") (pinfunction "VSS_N25") (pintype "passive"))
      (node (ref "U1") (pin "N27") (pinfunction "VSS_N27") (pintype "passive"))
      (node (ref "U1") (pin "N29") (pinfunction "VSS_N29") (pintype "passive"))
      (node (ref "U1") (pin "N31") (pinfunction "VSS_N31") (pintype "passive"))
      (node (ref "U1") (pin "N33") (pinfunction "VSS_N33") (pintype "passive"))
      (node (ref "U1") (pin "N6") (pinfunction "VSS_N6") (pintype "passive"))
      (node (ref "U1") (pin "N8") (pinfunction "VSS_N8") (pintype "passive"))
      (node (ref "U1") (pin "P11") (pinfunction "VSS_P11") (pintype "passive"))
      (node (ref "U1") (pin "P13") (pinfunction "VSS_P13") (pintype "passive"))
      (node (ref "U1") (pin "P15") (pinfunction "VSS_P15") (pintype "passive"))
      (node (ref "U1") (pin "P17") (pinfunction "VSS_P17") (pintype "passive"))
      (node (ref "U1") (pin "P20") (pinfunction "VSS_P20") (pintype "passive"))
      (node (ref "U1") (pin "P22") (pinfunction "VSS_P22") (pintype "passive"))
      (node (ref "U1") (pin "P24") (pinfunction "VSS_P24") (pintype "passive"))
      (node (ref "U1") (pin "P26") (pinfunction "VSS_P26") (pintype "passive"))
      (node (ref "U1") (pin "P28") (pinfunction "VSS_P28") (pintype "passive"))
      (node (ref "U1") (pin "P3") (pinfunction "VSS_P3") (pintype "passive"))
      (node (ref "U1") (pin "P30") (pinfunction "VSS_P30") (pintype "passive"))
      (node (ref "U1") (pin "P32") (pinfunction "VSS_P32") (pintype "passive"))
      (node (ref "U1") (pin "P5") (pinfunction "VSS_P5") (pintype "passive"))
      (node (ref "U1") (pin "P7") (pinfunction "VSS_P7") (pintype "passive"))
      (node (ref "U1") (pin "P9") (pinfunction "VSS_P9") (pintype "passive"))
      (node (ref "U1") (pin "R10") (pinfunction "VSS_R10") (pintype "passive"))
      (node (ref "U1") (pin "R12") (pinfunction "VSS_R12") (pintype "passive"))
      (node (ref "U1") (pin "R14") (pinfunction "VSS_R14") (pintype "passive"))
      (node (ref "U1") (pin "R16") (pinfunction "VSS_R16") (pintype "passive"))
      (node (ref "U1") (pin "R18") (pinfunction "VSS_R18") (pintype "passive"))
      (node (ref "U1") (pin "R19") (pinfunction "VSS_R19") (pintype "passive"))
      (node (ref "U1") (pin "R21") (pinfunction "VSS_R21") (pintype "passive"))
      (node (ref "U1") (pin "R23") (pinfunction "VSS_R23") (pintype "passive"))
      (node (ref "U1") (pin "R25") (pinfunction "VSS_R25") (pintype "passive"))
      (node (ref "U1") (pin "R27") (pinfunction "VSS_R27") (pintype "passive"))
      (node (ref "U1") (pin "R29") (pinfunction "VSS_R29") (pintype "passive"))
      (node (ref "U1") (pin "R31") (pinfunction "VSS_R31") (pintype "passive"))
      (node (ref "U1") (pin "R6") (pinfunction "VSS_R6") (pintype "passive"))
      (node (ref "U1") (pin "R8") (pinfunction "VSS_R8") (pintype "passive"))
      (node (ref "U1") (pin "T11") (pinfunction "VSS_T11") (pintype "passive"))
      (node (ref "U1") (pin "T13") (pinfunction "VSS_T13") (pintype "passive"))
      (node (ref "U1") (pin "T15") (pinfunction "VSS_T15") (pintype "passive"))
      (node (ref "U1") (pin "T17") (pinfunction "VSS_T17") (pintype "passive"))
      (node (ref "U1") (pin "T20") (pinfunction "VSS_T20") (pintype "passive"))
      (node (ref "U1") (pin "T22") (pinfunction "VSS_T22") (pintype "passive"))
      (node (ref "U1") (pin "T24") (pinfunction "VSS_T24") (pintype "passive"))
      (node (ref "U1") (pin "T26") (pinfunction "VSS_T26") (pintype "passive"))
      (node (ref "U1") (pin "T28") (pinfunction "VSS_T28") (pintype "passive"))
      (node (ref "U1") (pin "T30") (pinfunction "VSS_T30") (pintype "passive"))
      (node (ref "U1") (pin "T32") (pinfunction "VSS_T32") (pintype "passive"))
      (node (ref "U1") (pin "T34") (pinfunction "VSS_T34") (pintype "passive"))
      (node (ref "U1") (pin "T5") (pinfunction "VSS_T5") (pintype "passive"))
      (node (ref "U1") (pin "T7") (pinfunction "VSS_T7") (pintype "passive"))
      (node (ref "U1") (pin "T9") (pinfunction "VSS_T9") (pintype "passive"))
      (node (ref "U1") (pin "U10") (pinfunction "VSS_U10") (pintype "passive"))
      (node (ref "U1") (pin "U12") (pinfunction "VSS_U12") (pintype "passive"))
      (node (ref "U1") (pin "U14") (pinfunction "VSS_U14") (pintype "passive"))
      (node (ref "U1") (pin "U16") (pinfunction "VSS_U16") (pintype "passive"))
      (node (ref "U1") (pin "U18") (pinfunction "VSS_U18") (pintype "passive"))
      (node (ref "U1") (pin "U19") (pinfunction "VSS_U19") (pintype "passive"))
      (node (ref "U1") (pin "U21") (pinfunction "VSS_U21") (pintype "passive"))
      (node (ref "U1") (pin "U23") (pinfunction "VSS_U23") (pintype "passive"))
      (node (ref "U1") (pin "U25") (pinfunction "VSS_U25") (pintype "passive"))
      (node (ref "U1") (pin "U27") (pinfunction "VSS_U27") (pintype "passive"))
      (node (ref "U1") (pin "U29") (pinfunction "VSS_U29") (pintype "passive"))
      (node (ref "U1") (pin "U31") (pinfunction "VSS_U31") (pintype "passive"))
      (node (ref "U1") (pin "U32") (pinfunction "VSS_U32") (pintype "passive"))
      (node (ref "U1") (pin "U4") (pinfunction "VSS_U4") (pintype "passive"))
      (node (ref "U1") (pin "U6") (pinfunction "VSS_U6") (pintype "passive"))
      (node (ref "U1") (pin "U8") (pinfunction "VSS_U8") (pintype "passive"))
      (node (ref "U1") (pin "V1") (pinfunction "VSS_V1") (pintype "passive"))
      (node (ref "U1") (pin "V11") (pinfunction "VSS_V11") (pintype "passive"))
      (node (ref "U1") (pin "V13") (pinfunction "VSS_V13") (pintype "passive"))
      (node (ref "U1") (pin "V15") (pinfunction "VSS_V15") (pintype "passive"))
      (node (ref "U1") (pin "V17") (pinfunction "VSS_V17") (pintype "passive"))
      (node (ref "U1") (pin "V20") (pinfunction "VSS_V20") (pintype "passive"))
      (node (ref "U1") (pin "V22") (pinfunction "VSS_V22") (pintype "passive"))
      (node (ref "U1") (pin "V24") (pinfunction "VSS_V24") (pintype "passive"))
      (node (ref "U1") (pin "V26") (pinfunction "VSS_V26") (pintype "passive"))
      (node (ref "U1") (pin "V28") (pinfunction "VSS_V28") (pintype "passive"))
      (node (ref "U1") (pin "V3") (pinfunction "VSS_V3") (pintype "passive"))
      (node (ref "U1") (pin "V30") (pinfunction "VSS_V30") (pintype "passive"))
      (node (ref "U1") (pin "V5") (pinfunction "VSS_V5") (pintype "passive"))
      (node (ref "U1") (pin "V7") (pinfunction "VSS_V7") (pintype "passive"))
      (node (ref "U1") (pin "V9") (pinfunction "VSS_V9") (pintype "passive"))
      (node (ref "U1") (pin "W11") (pinfunction "VSS_W11") (pintype "passive"))
      (node (ref "U1") (pin "W13") (pinfunction "VSS_W13") (pintype "passive"))
      (node (ref "U1") (pin "W15") (pinfunction "VSS_W15") (pintype "passive"))
      (node (ref "U1") (pin "W17") (pinfunction "VSS_W17") (pintype "passive"))
      (node (ref "U1") (pin "W20") (pinfunction "VSS_W20") (pintype "passive"))
      (node (ref "U1") (pin "W22") (pinfunction "VSS_W22") (pintype "passive"))
      (node (ref "U1") (pin "W24") (pinfunction "VSS_W24") (pintype "passive"))
      (node (ref "U1") (pin "W26") (pinfunction "VSS_W26") (pintype "passive"))
      (node (ref "U1") (pin "W28") (pinfunction "VSS_W28") (pintype "passive"))
      (node (ref "U1") (pin "W30") (pinfunction "VSS_W30") (pintype "passive"))
      (node (ref "U1") (pin "W32") (pinfunction "VSS_W32") (pintype "passive"))
      (node (ref "U1") (pin "W34") (pinfunction "VSS_W34") (pintype "passive"))
      (node (ref "U1") (pin "W36") (pinfunction "VSS_W36") (pintype "passive"))
      (node (ref "U1") (pin "W7") (pinfunction "VSS_W7") (pintype "passive"))
      (node (ref "U1") (pin "W9") (pinfunction "VSS_W9") (pintype "passive"))
      (node (ref "U1") (pin "Y10") (pinfunction "VSS_Y10") (pintype "passive"))
      (node (ref "U1") (pin "Y12") (pinfunction "VSS_Y12") (pintype "passive"))
      (node (ref "U1") (pin "Y14") (pinfunction "VSS_Y14") (pintype "passive"))
      (node (ref "U1") (pin "Y16") (pinfunction "VSS_Y16") (pintype "passive"))
      (node (ref "U1") (pin "Y18") (pinfunction "VSS_Y18") (pintype "passive"))
      (node (ref "U1") (pin "Y19") (pinfunction "VSS_Y19") (pintype "passive"))
      (node (ref "U1") (pin "Y21") (pinfunction "VSS_Y21") (pintype "passive"))
      (node (ref "U1") (pin "Y23") (pinfunction "VSS_Y23") (pintype "passive"))
      (node (ref "U1") (pin "Y25") (pinfunction "VSS_Y25") (pintype "passive"))
      (node (ref "U1") (pin "Y27") (pinfunction "VSS_Y27") (pintype "passive"))
      (node (ref "U1") (pin "Y29") (pinfunction "VSS_Y29") (pintype "passive"))
      (node (ref "U1") (pin "Y31") (pinfunction "VSS_Y31") (pintype "passive"))
      (node (ref "U1") (pin "Y33") (pinfunction "VSS_Y33") (pintype "passive"))
      (node (ref "U1") (pin "Y5") (pinfunction "VSS_Y5") (pintype "passive"))
      (node (ref "U1") (pin "Y6") (pinfunction "VSS_Y6") (pintype "passive"))
      (node (ref "U1") (pin "Y8") (pinfunction "VSS_Y8") (pintype "passive"))
    )
  )
)
